# dw08aRev3.net
KiCad netlist of a schematic drawn in EAGLE
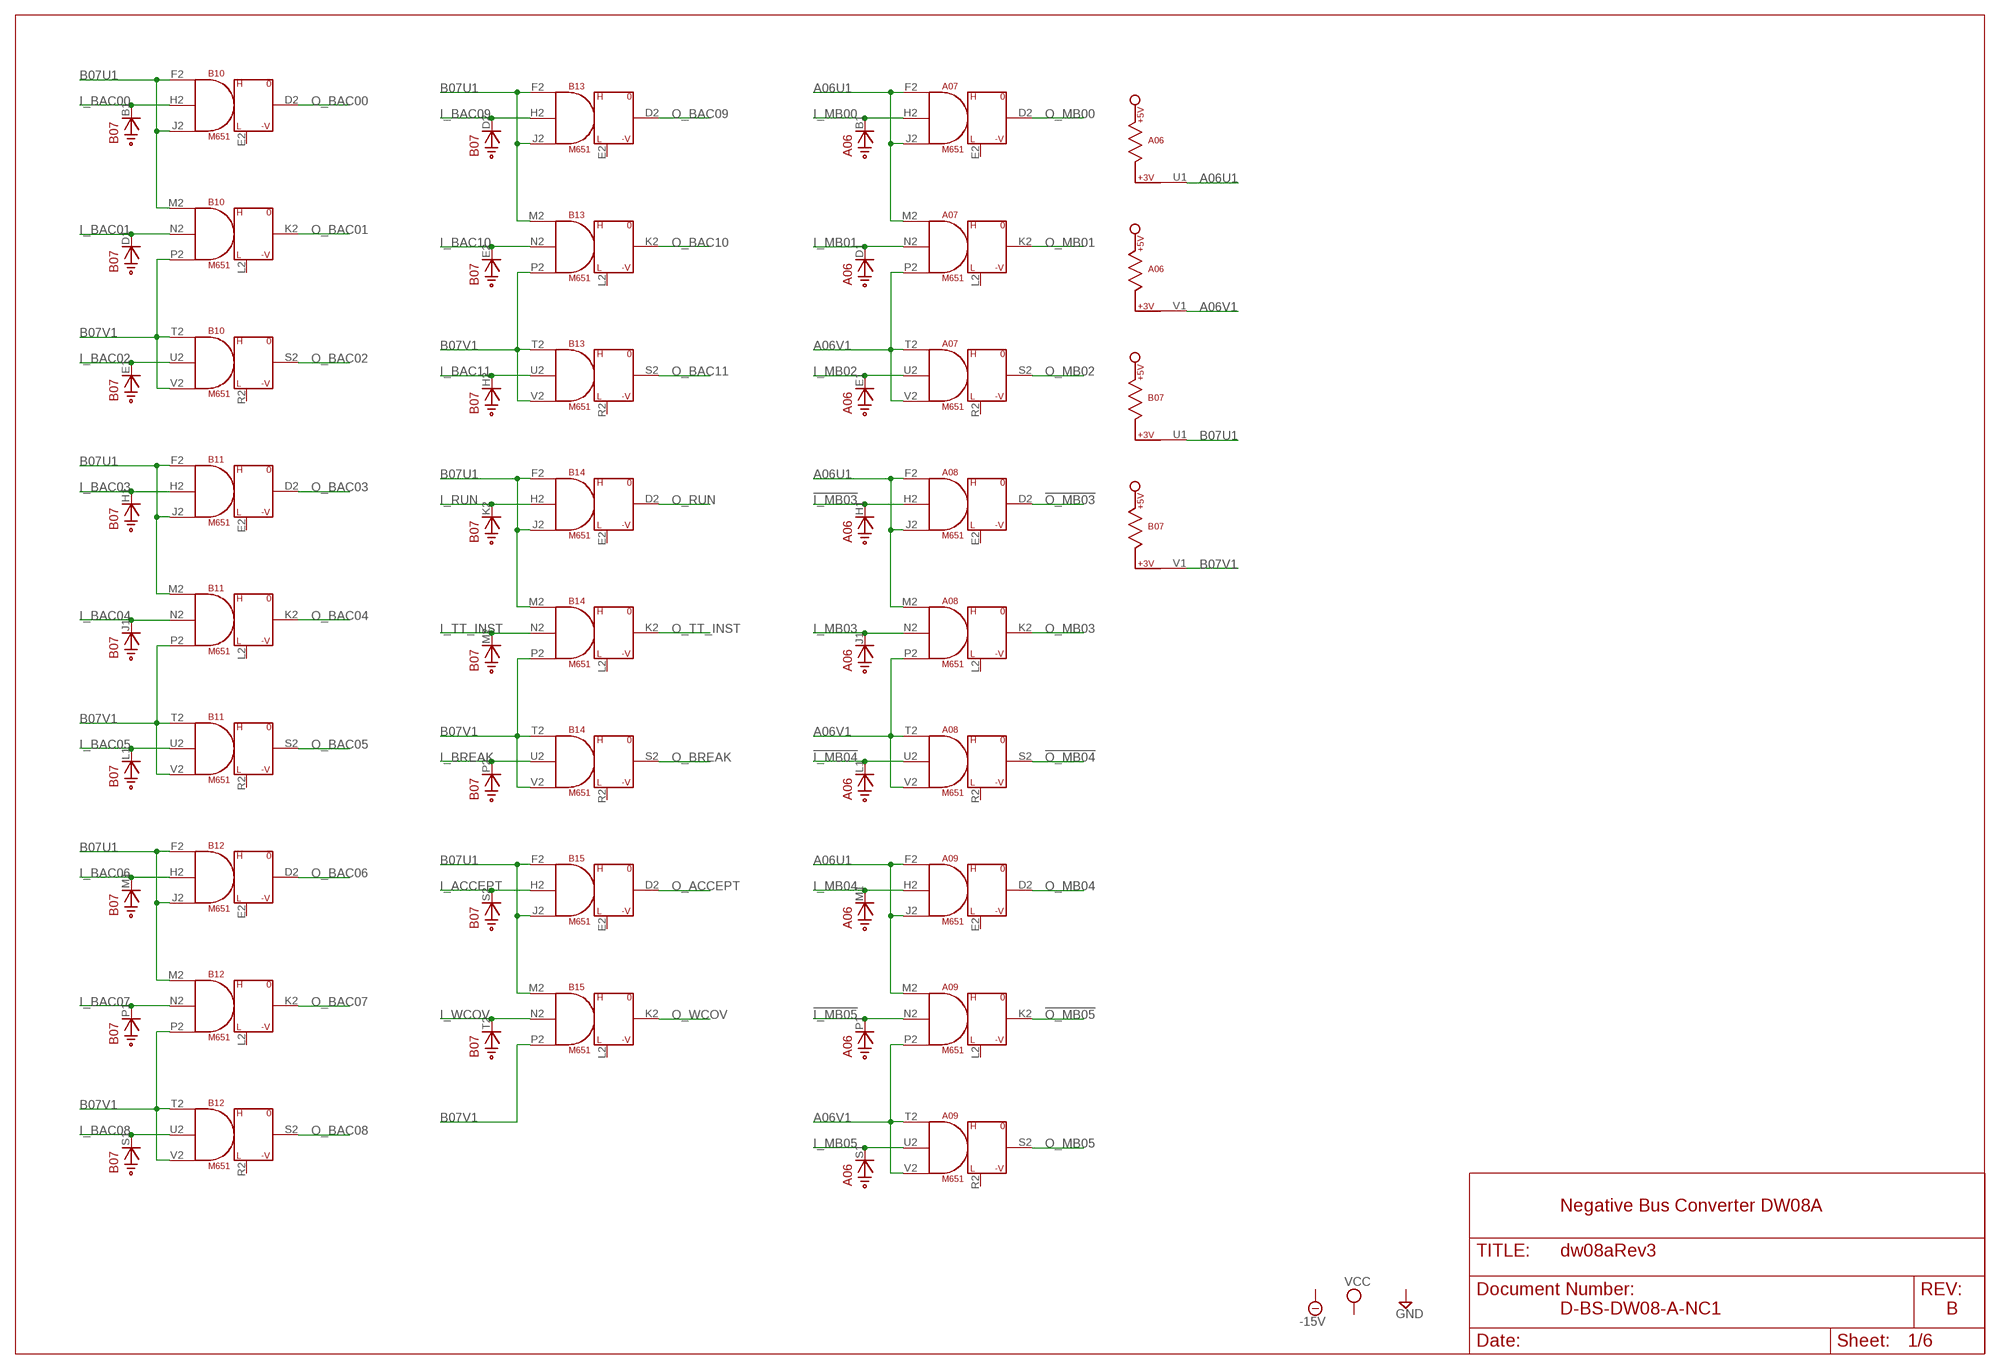
[diagram p0: schematic, sheet 1]
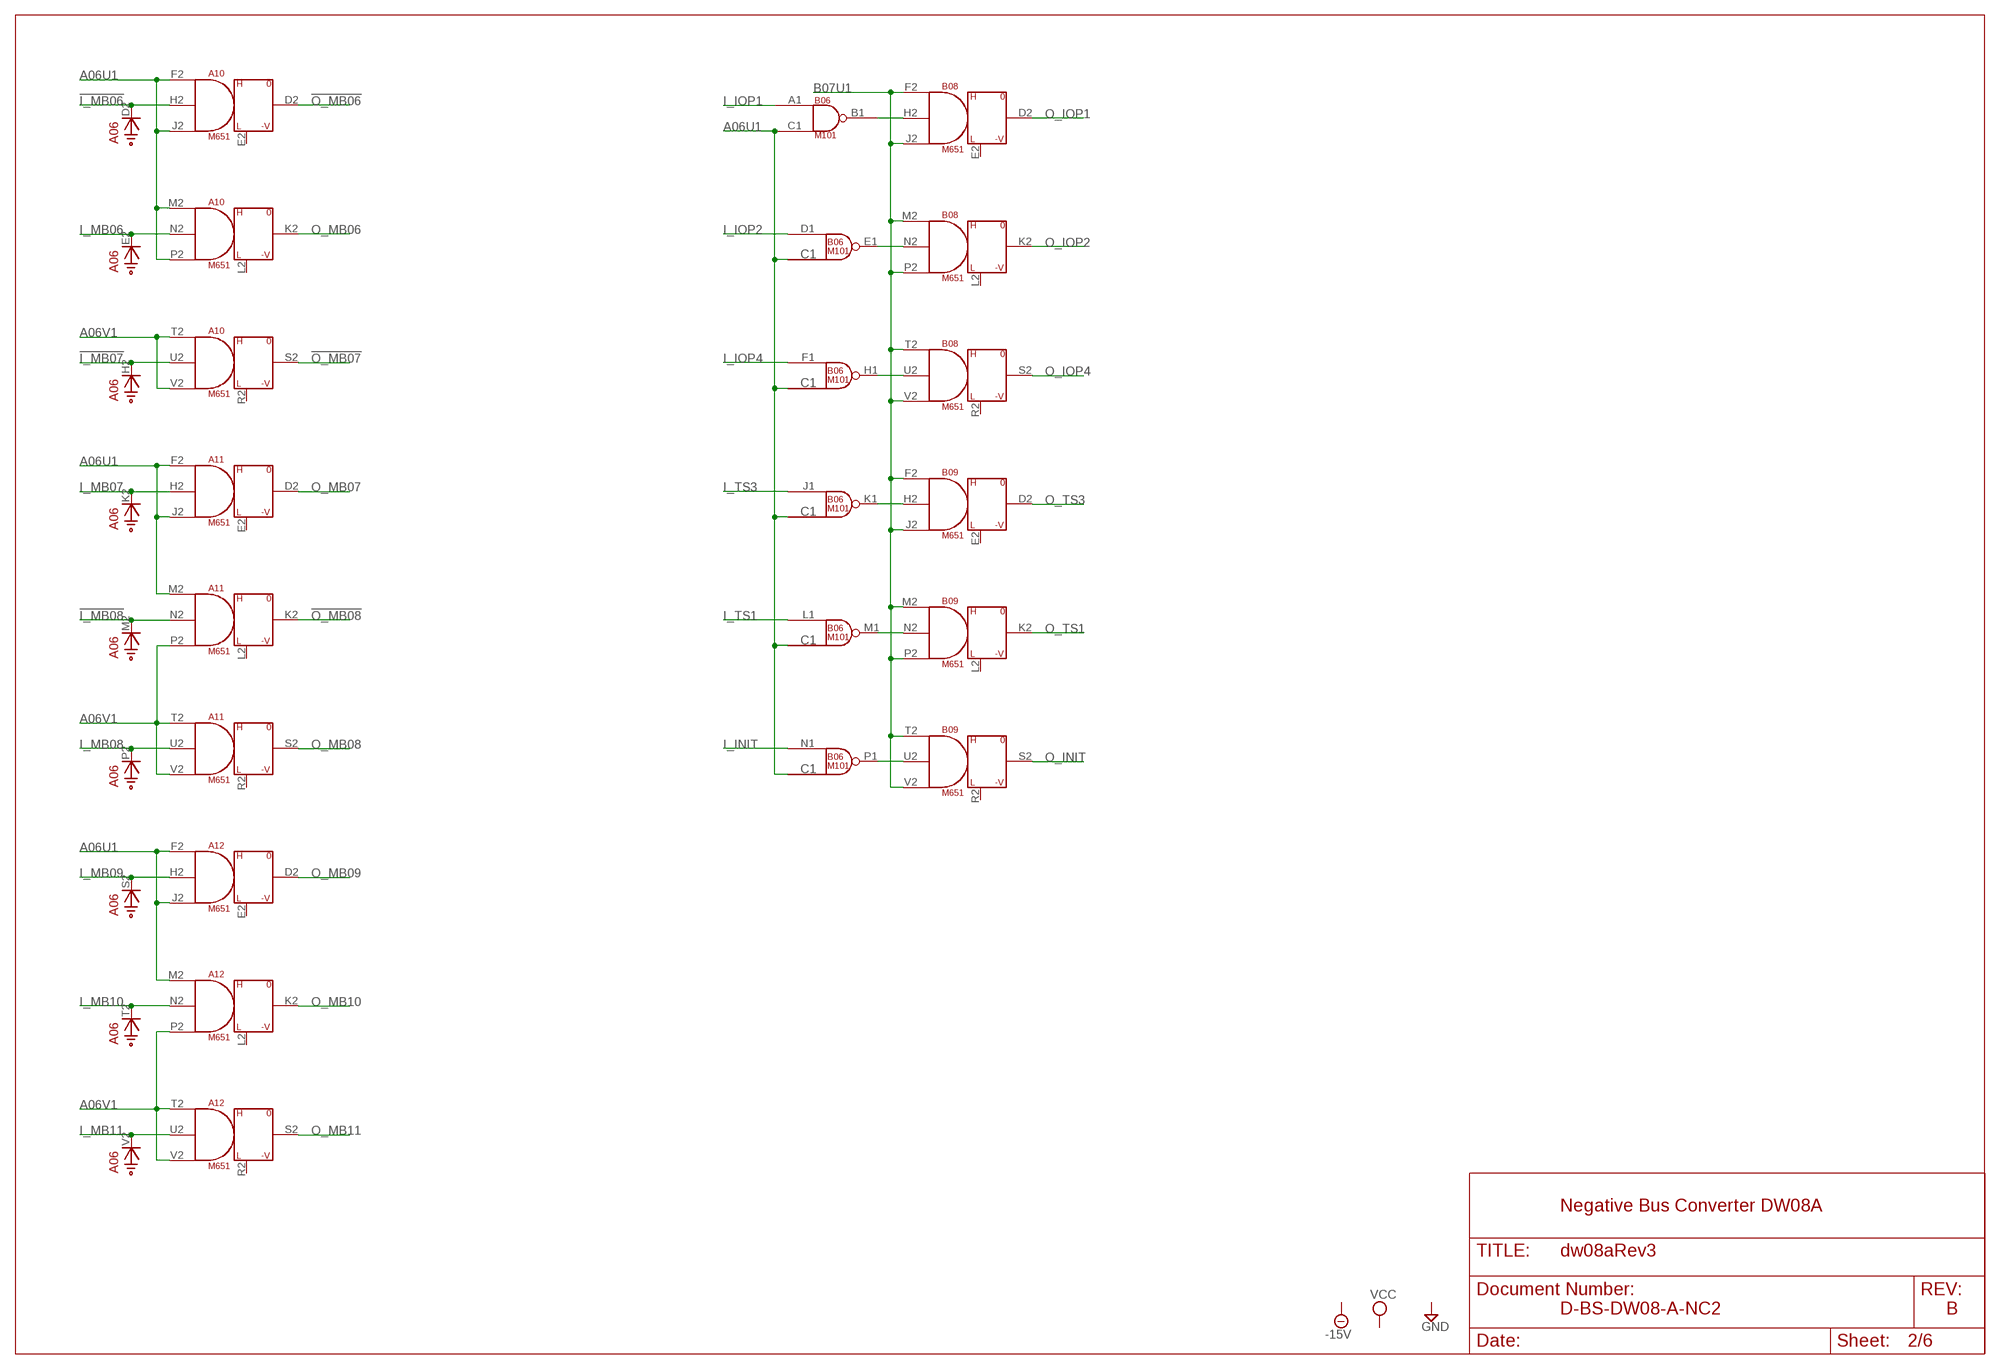
[diagram p1: schematic, sheet 2]
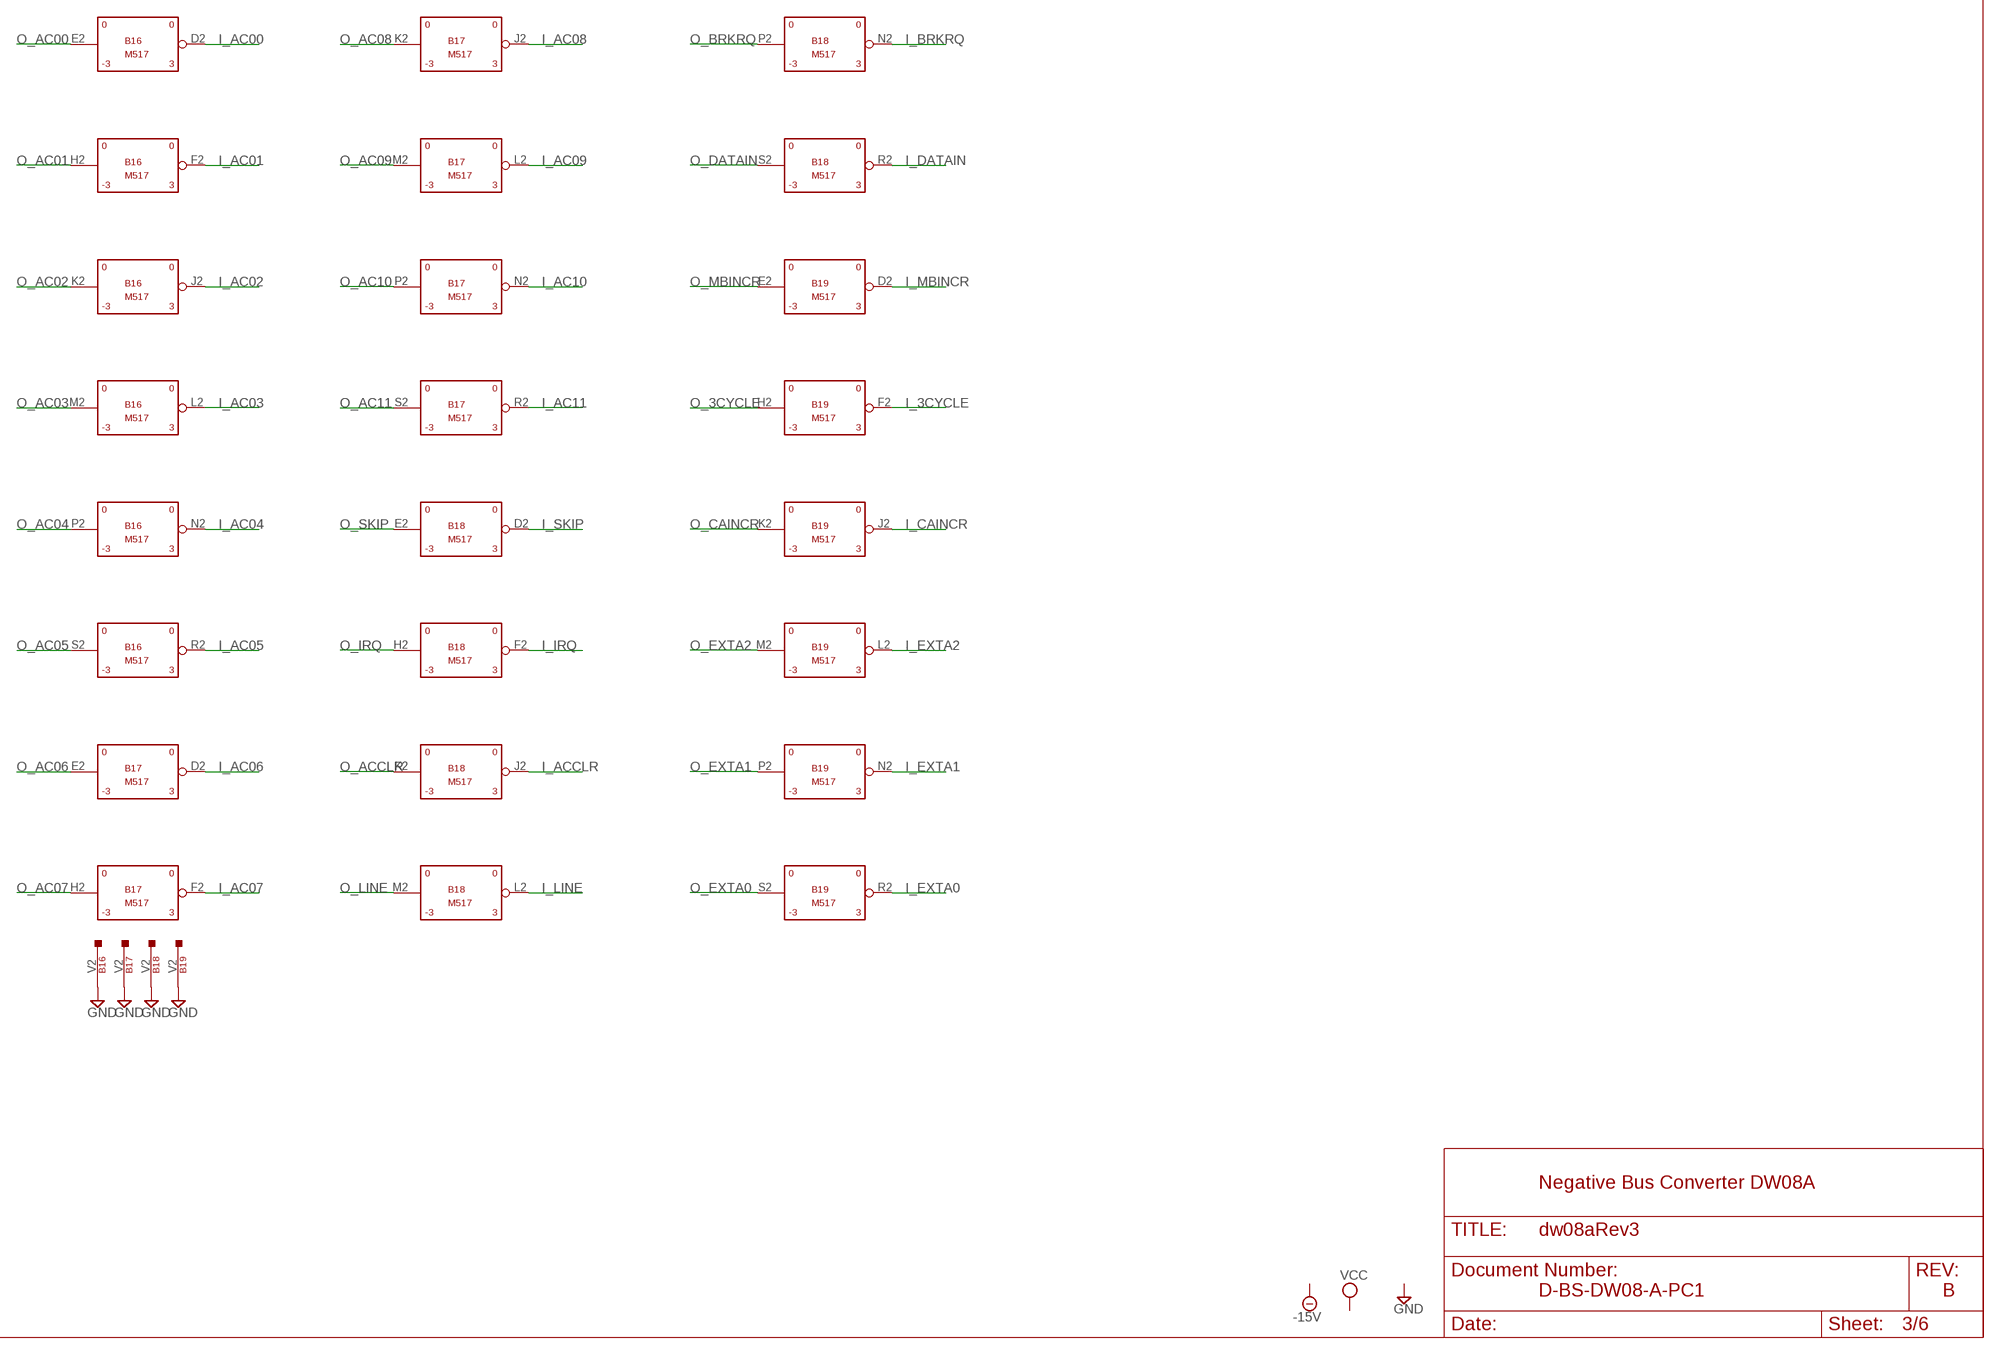
[diagram p2: schematic, sheet 3]
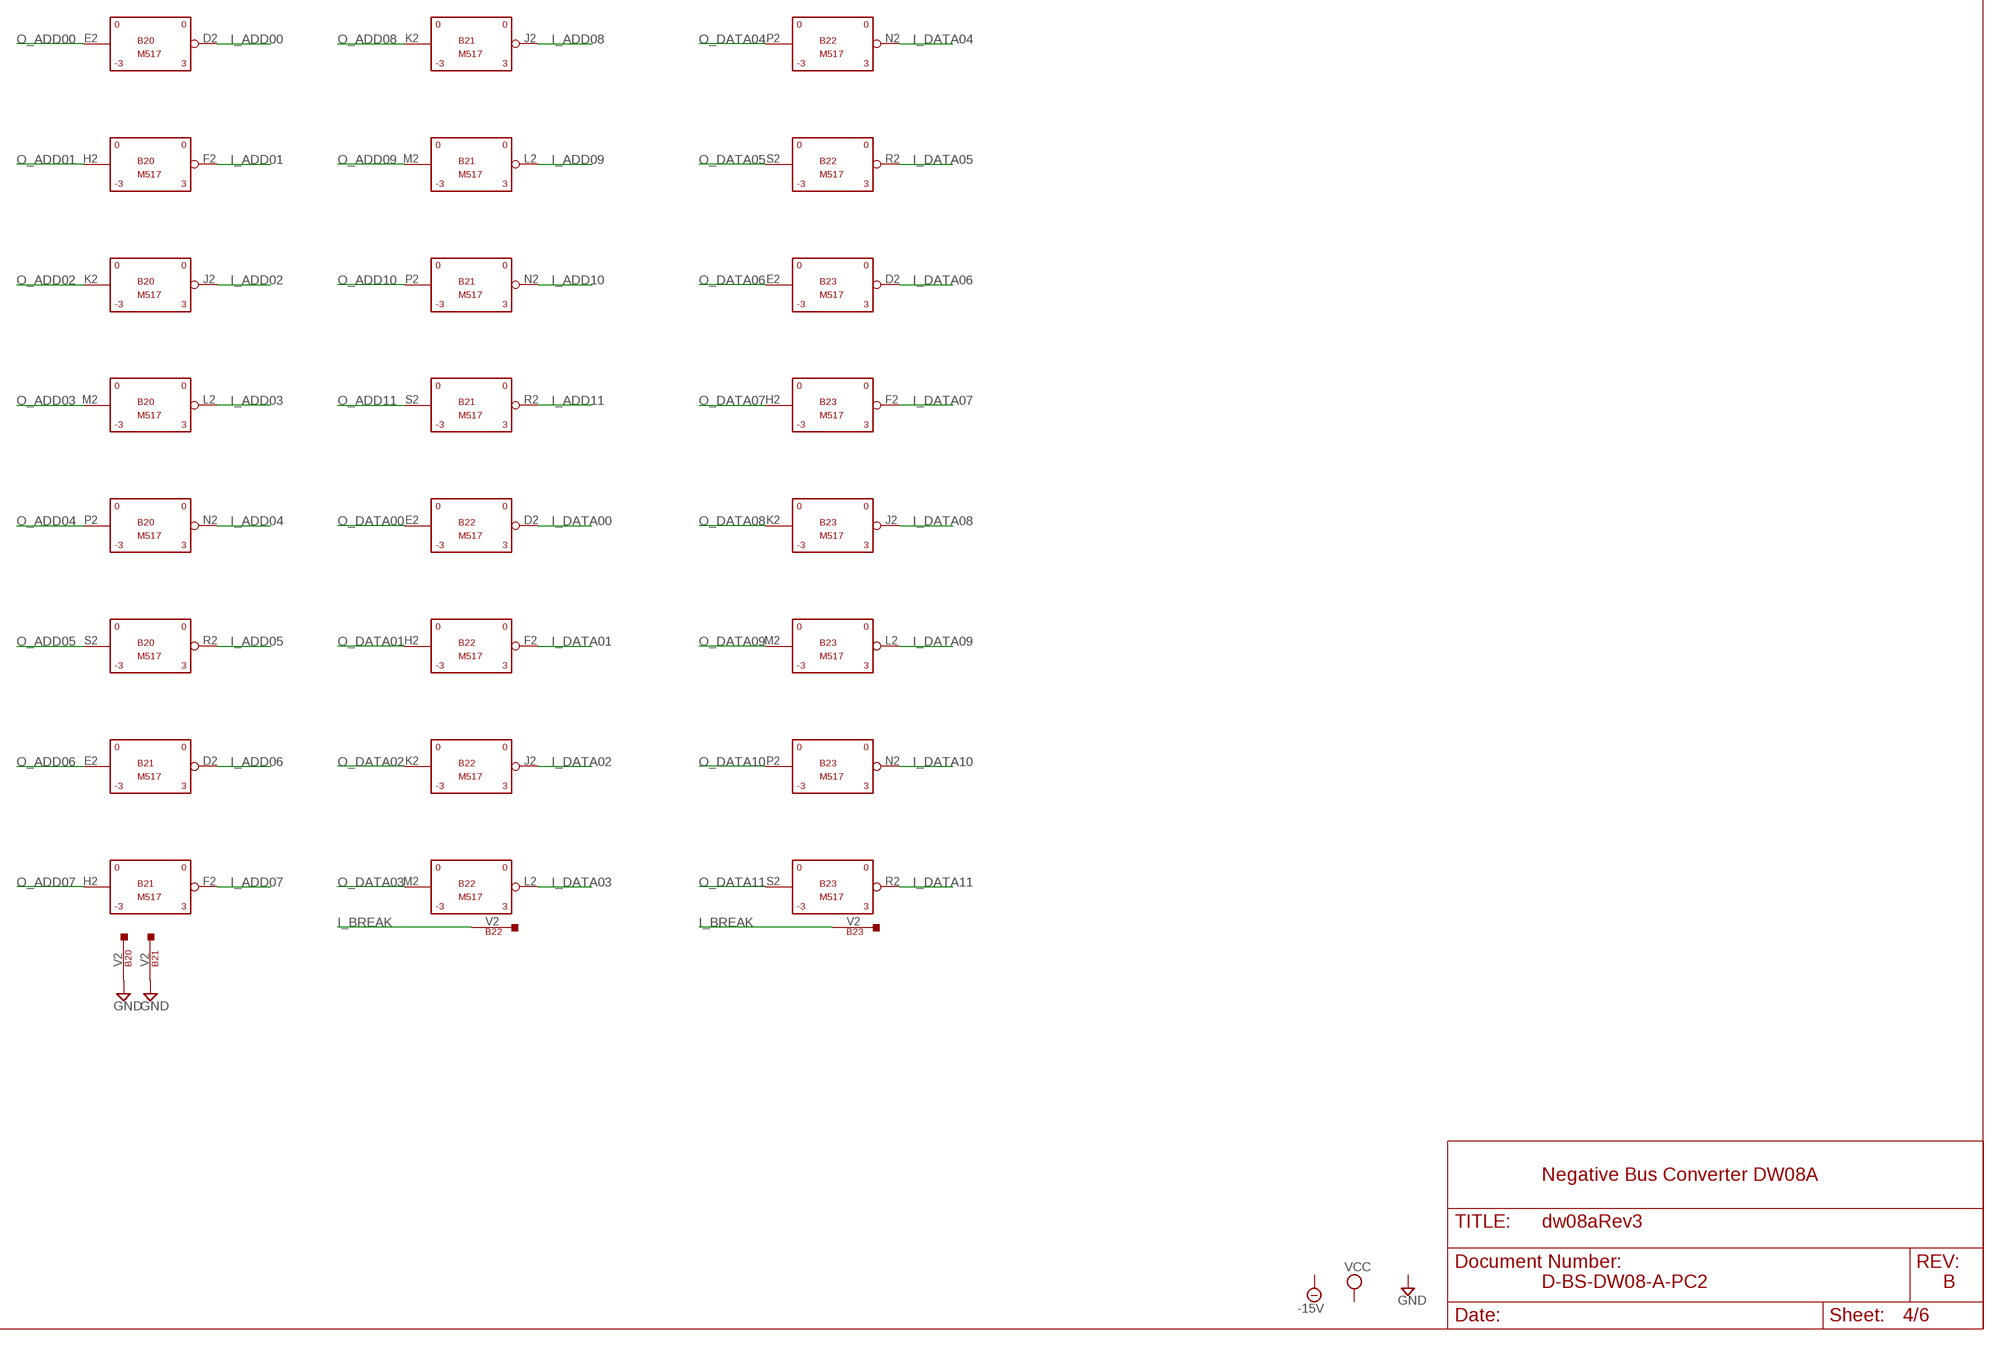
[diagram p3: schematic, sheet 4]
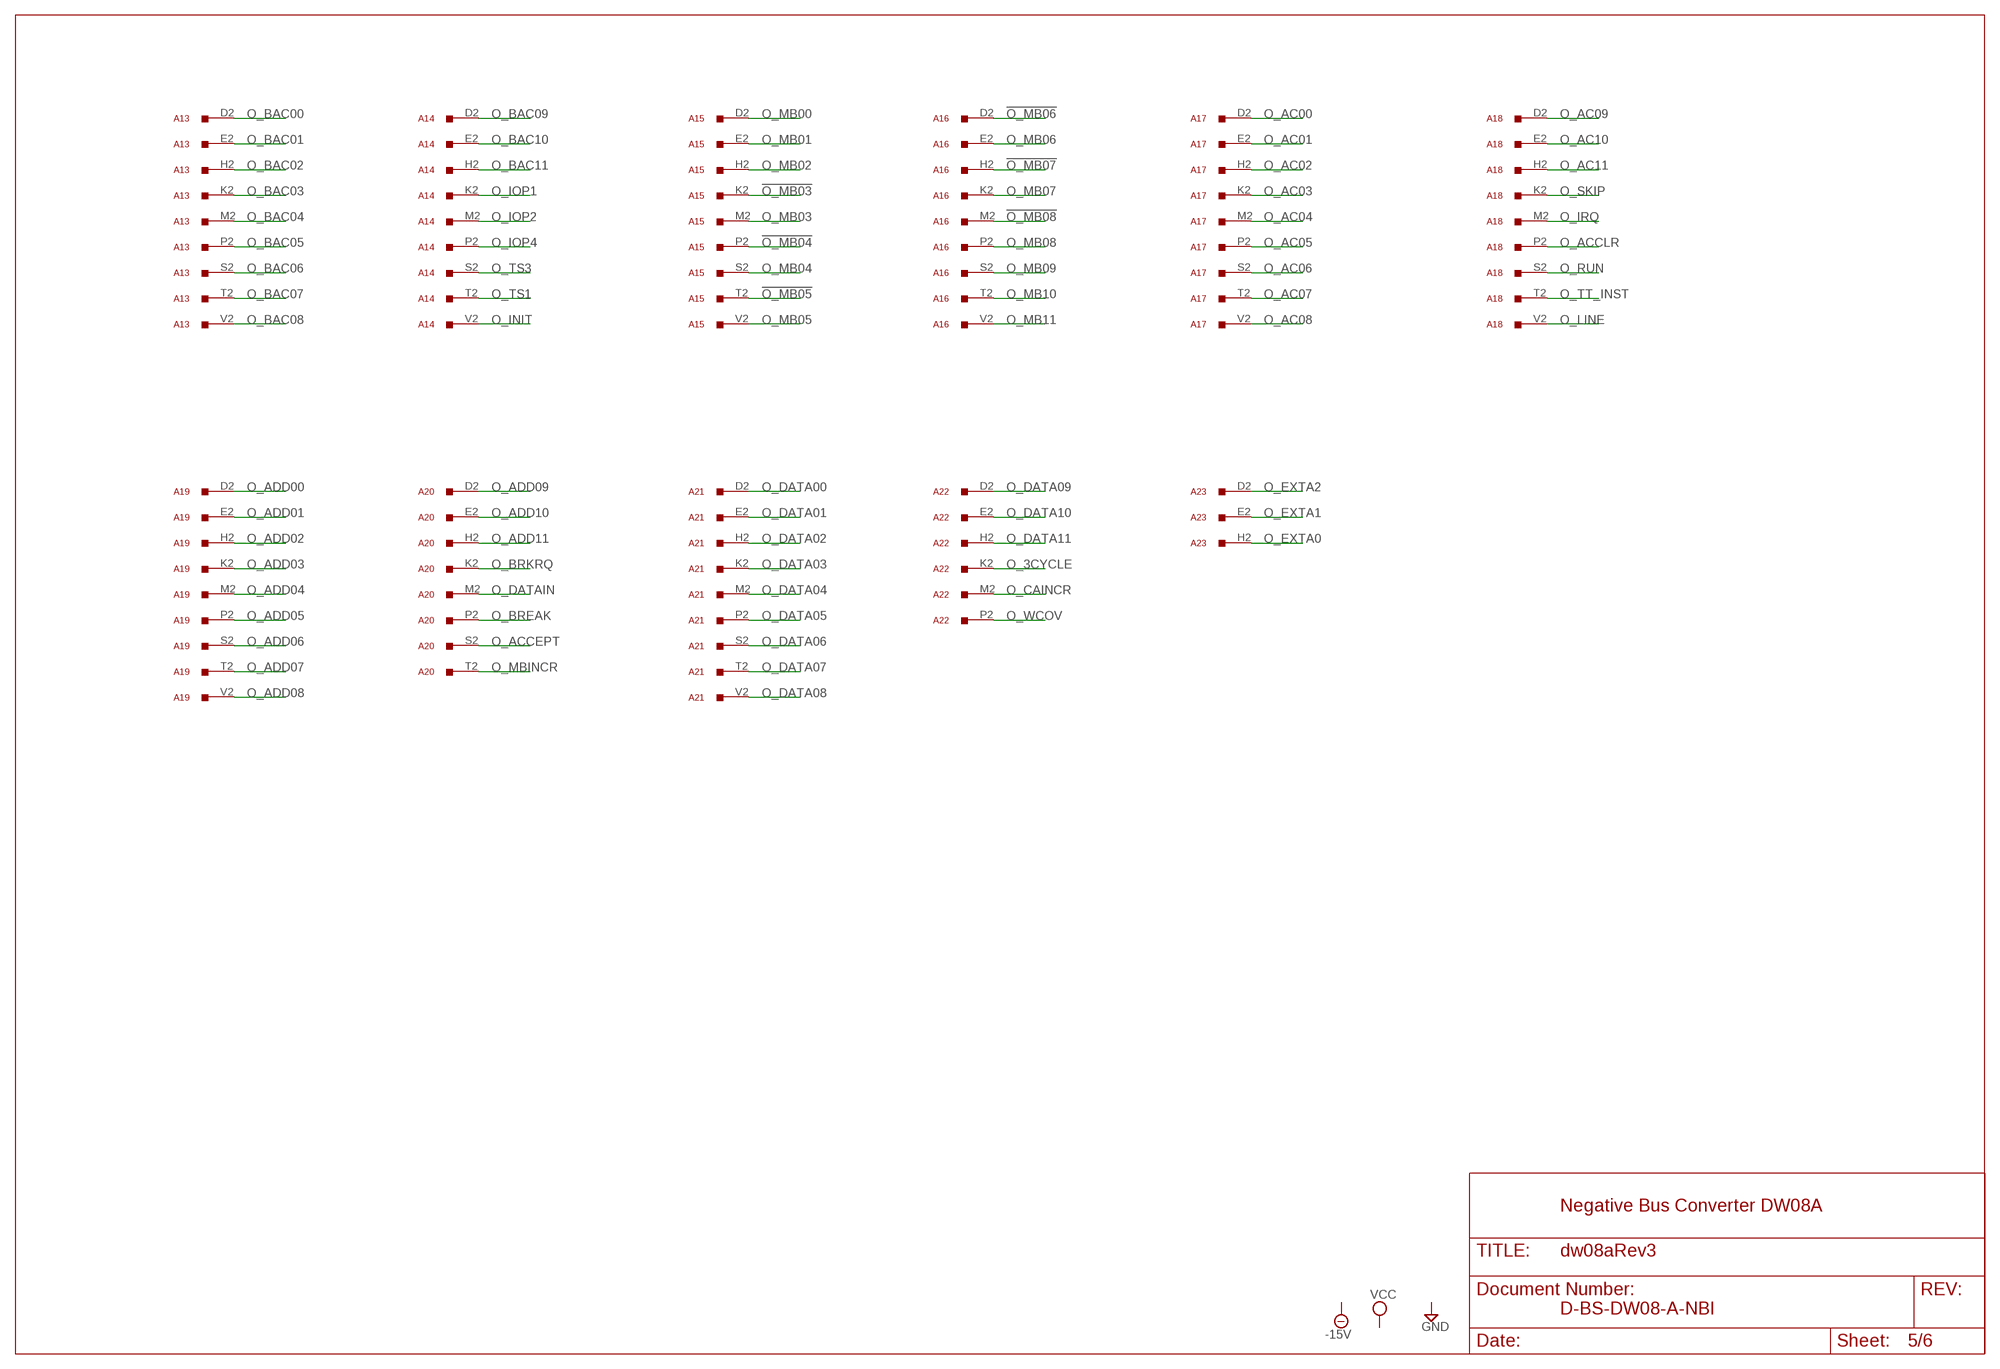
[diagram p4: schematic, sheet 5]
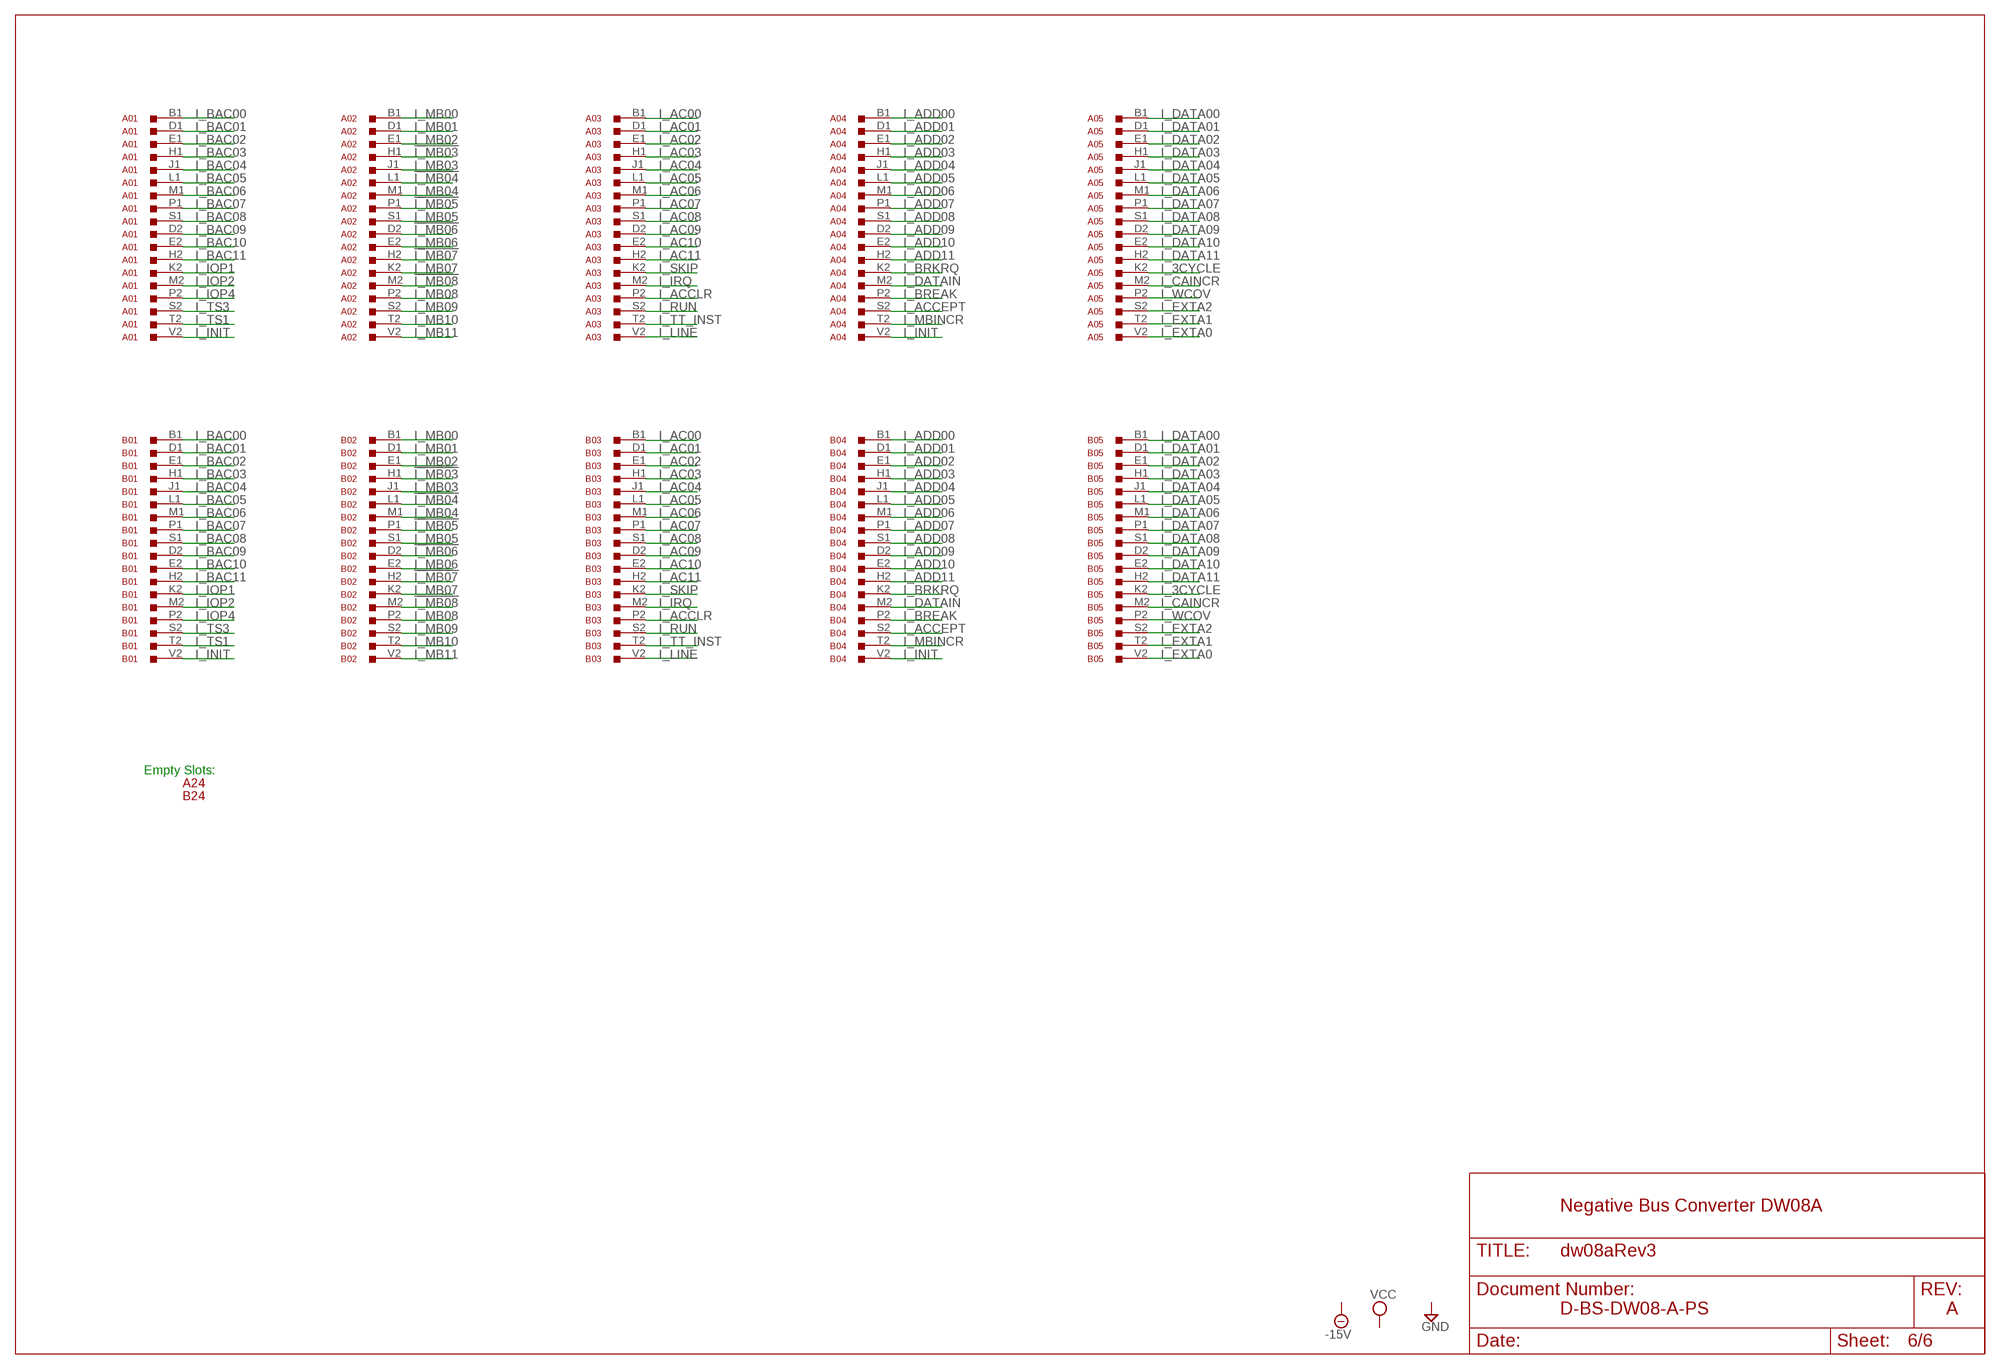
[diagram p5: schematic, sheet 6]

(export (version "E")
  (design (tool "Eeschema 10.0.6"))
  (components
    (comp (ref "B20")
      (value "M517")
      (footprint "eagle-import:H807")
      (libsource (lib "eagle-import") (part "M517"))
    )
    (comp (ref "B21")
      (value "M517")
      (footprint "eagle-import:H807")
      (libsource (lib "eagle-import") (part "M517"))
    )
    (comp (ref "B22")
      (value "M517")
      (footprint "eagle-import:H807")
      (libsource (lib "eagle-import") (part "M517"))
    )
    (comp (ref "B23")
      (value "M517")
      (footprint "eagle-import:H807")
      (libsource (lib "eagle-import") (part "M517"))
    )
    (comp (ref "B16")
      (value "M517")
      (footprint "eagle-import:H807")
      (libsource (lib "eagle-import") (part "M517"))
    )
    (comp (ref "B17")
      (value "M517")
      (footprint "eagle-import:H807")
      (libsource (lib "eagle-import") (part "M517"))
    )
    (comp (ref "B18")
      (value "M517")
      (footprint "eagle-import:H807")
      (libsource (lib "eagle-import") (part "M517"))
    )
    (comp (ref "B19")
      (value "M517")
      (footprint "eagle-import:H807")
      (libsource (lib "eagle-import") (part "M517"))
    )
    (comp (ref "A13")
      (value "W011")
      (footprint "eagle-import:H807")
      (libsource (lib "eagle-import") (part "W011"))
    )
    (comp (ref "A14")
      (value "W011")
      (footprint "eagle-import:H807")
      (libsource (lib "eagle-import") (part "W011"))
    )
    (comp (ref "A15")
      (value "W011")
      (footprint "eagle-import:H807")
      (libsource (lib "eagle-import") (part "W011"))
    )
    (comp (ref "A16")
      (value "W011")
      (footprint "eagle-import:H807")
      (libsource (lib "eagle-import") (part "W011"))
    )
    (comp (ref "A17")
      (value "W011")
      (footprint "eagle-import:H807")
      (libsource (lib "eagle-import") (part "W011"))
    )
    (comp (ref "A18")
      (value "W011")
      (footprint "eagle-import:H807")
      (libsource (lib "eagle-import") (part "W011"))
    )
    (comp (ref "A19")
      (value "W011")
      (footprint "eagle-import:H807")
      (libsource (lib "eagle-import") (part "W011"))
    )
    (comp (ref "A20")
      (value "W011")
      (footprint "eagle-import:H807")
      (libsource (lib "eagle-import") (part "W011"))
    )
    (comp (ref "A21")
      (value "W011")
      (footprint "eagle-import:H807")
      (libsource (lib "eagle-import") (part "W011"))
    )
    (comp (ref "A22")
      (value "W011")
      (footprint "eagle-import:H807")
      (libsource (lib "eagle-import") (part "W011"))
    )
    (comp (ref "A23")
      (value "W011")
      (footprint "eagle-import:H807")
      (libsource (lib "eagle-import") (part "W011"))
    )
    (comp (ref "A06")
      (value "M907")
      (footprint "eagle-import:H807")
      (libsource (lib "eagle-import") (part "M907"))
    )
    (comp (ref "A10")
      (value "M651")
      (footprint "eagle-import:H807")
      (libsource (lib "eagle-import") (part "M651"))
    )
    (comp (ref "A11")
      (value "M651")
      (footprint "eagle-import:H807")
      (libsource (lib "eagle-import") (part "M651"))
    )
    (comp (ref "A12")
      (value "M651")
      (footprint "eagle-import:H807")
      (libsource (lib "eagle-import") (part "M651"))
    )
    (comp (ref "B06")
      (value "M101")
      (footprint "eagle-import:H807")
      (libsource (lib "eagle-import") (part "M101"))
    )
    (comp (ref "B08")
      (value "M651")
      (footprint "eagle-import:H807")
      (libsource (lib "eagle-import") (part "M651"))
    )
    (comp (ref "B09")
      (value "M651")
      (footprint "eagle-import:H807")
      (libsource (lib "eagle-import") (part "M651"))
    )
    (comp (ref "A07")
      (value "M651")
      (footprint "eagle-import:H807")
      (libsource (lib "eagle-import") (part "M651"))
    )
    (comp (ref "A08")
      (value "M651")
      (footprint "eagle-import:H807")
      (libsource (lib "eagle-import") (part "M651"))
    )
    (comp (ref "A09")
      (value "M651")
      (footprint "eagle-import:H807")
      (libsource (lib "eagle-import") (part "M651"))
    )
    (comp (ref "B07")
      (value "M907")
      (footprint "eagle-import:H807")
      (libsource (lib "eagle-import") (part "M907"))
    )
    (comp (ref "B10")
      (value "M651")
      (footprint "eagle-import:H807")
      (libsource (lib "eagle-import") (part "M651"))
    )
    (comp (ref "B11")
      (value "M651")
      (footprint "eagle-import:H807")
      (libsource (lib "eagle-import") (part "M651"))
    )
    (comp (ref "B12")
      (value "M651")
      (footprint "eagle-import:H807")
      (libsource (lib "eagle-import") (part "M651"))
    )
    (comp (ref "B13")
      (value "M651")
      (footprint "eagle-import:H807")
      (libsource (lib "eagle-import") (part "M651"))
    )
    (comp (ref "B14")
      (value "M651")
      (footprint "eagle-import:H807")
      (libsource (lib "eagle-import") (part "M651"))
    )
    (comp (ref "B15")
      (value "M651")
      (footprint "eagle-import:H807")
      (libsource (lib "eagle-import") (part "M651"))
    )
    (comp (ref "A01")
      (value "M903")
      (footprint "eagle-import:H807")
      (libsource (lib "eagle-import") (part "M903"))
    )
    (comp (ref "A02")
      (value "M903")
      (footprint "eagle-import:H807")
      (libsource (lib "eagle-import") (part "M903"))
    )
    (comp (ref "A03")
      (value "M903")
      (footprint "eagle-import:H807")
      (libsource (lib "eagle-import") (part "M903"))
    )
    (comp (ref "A04")
      (value "M903")
      (footprint "eagle-import:H807")
      (libsource (lib "eagle-import") (part "M903"))
    )
    (comp (ref "A05")
      (value "M903")
      (footprint "eagle-import:H807")
      (libsource (lib "eagle-import") (part "M903"))
    )
    (comp (ref "A24")
      (value "H807")
      (footprint "eagle-import:H807")
      (libsource (lib "eagle-import") (part "H807"))
    )
    (comp (ref "B01")
      (value "M903")
      (footprint "eagle-import:H807")
      (libsource (lib "eagle-import") (part "M903"))
    )
    (comp (ref "B02")
      (value "M903")
      (footprint "eagle-import:H807")
      (libsource (lib "eagle-import") (part "M903"))
    )
    (comp (ref "B03")
      (value "M903")
      (footprint "eagle-import:H807")
      (libsource (lib "eagle-import") (part "M903"))
    )
    (comp (ref "B04")
      (value "M903")
      (footprint "eagle-import:H807")
      (libsource (lib "eagle-import") (part "M903"))
    )
    (comp (ref "B05")
      (value "M903")
      (footprint "eagle-import:H807")
      (libsource (lib "eagle-import") (part "M903"))
    )
    (comp (ref "B24")
      (value "H807")
      (footprint "eagle-import:H807")
      (libsource (lib "eagle-import") (part "H807"))
    )
  )
  (nets
    (net (code "2") (name "A06U1") (class "Default")
      (node (ref "A06") (pin "U1") (pinfunction "P$1_U1") (pintype "passive"))
      (node (ref "A07") (pin "F2") (pinfunction "IN1_F2") (pintype "input"))
      (node (ref "A07") (pin "J2") (pinfunction "IN3_J2") (pintype "input"))
      (node (ref "A07") (pin "M2") (pinfunction "IN1_M2") (pintype "input"))
      (node (ref "A08") (pin "F2") (pinfunction "IN1_F2") (pintype "input"))
      (node (ref "A08") (pin "J2") (pinfunction "IN3_J2") (pintype "input"))
      (node (ref "A08") (pin "M2") (pinfunction "IN1_M2") (pintype "input"))
      (node (ref "A09") (pin "F2") (pinfunction "IN1_F2") (pintype "input"))
      (node (ref "A09") (pin "J2") (pinfunction "IN3_J2") (pintype "input"))
      (node (ref "A09") (pin "M2") (pinfunction "IN1_M2") (pintype "input"))
      (node (ref "A10") (pin "F2") (pinfunction "IN1_F2") (pintype "input"))
      (node (ref "A10") (pin "J2") (pinfunction "IN3_J2") (pintype "input"))
      (node (ref "A10") (pin "M2") (pinfunction "IN1_M2") (pintype "input"))
      (node (ref "A10") (pin "P2") (pinfunction "IN3_P2") (pintype "input"))
      (node (ref "A11") (pin "F2") (pinfunction "IN1_F2") (pintype "input"))
      (node (ref "A11") (pin "J2") (pinfunction "IN3_J2") (pintype "input"))
      (node (ref "A11") (pin "M2") (pinfunction "IN1_M2") (pintype "input"))
      (node (ref "A12") (pin "F2") (pinfunction "IN1_F2") (pintype "input"))
      (node (ref "A12") (pin "J2") (pinfunction "IN3_J2") (pintype "input"))
      (node (ref "A12") (pin "M2") (pinfunction "IN1_M2") (pintype "input"))
      (node (ref "B06") (pin "C1") (pinfunction "IN2_C1") (pintype "input"))
    )
    (net (code "3") (name "A06V1") (class "Default")
      (node (ref "A06") (pin "V1") (pinfunction "P$1_V1") (pintype "passive"))
      (node (ref "A07") (pin "P2") (pinfunction "IN3_P2") (pintype "input"))
      (node (ref "A07") (pin "T2") (pinfunction "IN1_T2") (pintype "input"))
      (node (ref "A07") (pin "V2") (pinfunction "IN3_V2") (pintype "input"))
      (node (ref "A08") (pin "P2") (pinfunction "IN3_P2") (pintype "input"))
      (node (ref "A08") (pin "T2") (pinfunction "IN1_T2") (pintype "input"))
      (node (ref "A08") (pin "V2") (pinfunction "IN3_V2") (pintype "input"))
      (node (ref "A09") (pin "P2") (pinfunction "IN3_P2") (pintype "input"))
      (node (ref "A09") (pin "T2") (pinfunction "IN1_T2") (pintype "input"))
      (node (ref "A09") (pin "V2") (pinfunction "IN3_V2") (pintype "input"))
      (node (ref "A10") (pin "T2") (pinfunction "IN1_T2") (pintype "input"))
      (node (ref "A10") (pin "V2") (pinfunction "IN3_V2") (pintype "input"))
      (node (ref "A11") (pin "P2") (pinfunction "IN3_P2") (pintype "input"))
      (node (ref "A11") (pin "T2") (pinfunction "IN1_T2") (pintype "input"))
      (node (ref "A11") (pin "V2") (pinfunction "IN3_V2") (pintype "input"))
      (node (ref "A12") (pin "P2") (pinfunction "IN3_P2") (pintype "input"))
      (node (ref "A12") (pin "T2") (pinfunction "IN1_T2") (pintype "input"))
      (node (ref "A12") (pin "V2") (pinfunction "IN3_V2") (pintype "input"))
    )
    (net (code "4") (name "B07U1") (class "Default")
      (node (ref "B07") (pin "U1") (pinfunction "P$1_U1") (pintype "passive"))
      (node (ref "B08") (pin "F2") (pinfunction "IN1_F2") (pintype "input"))
      (node (ref "B08") (pin "J2") (pinfunction "IN3_J2") (pintype "input"))
      (node (ref "B08") (pin "M2") (pinfunction "IN1_M2") (pintype "input"))
      (node (ref "B08") (pin "P2") (pinfunction "IN3_P2") (pintype "input"))
      (node (ref "B08") (pin "T2") (pinfunction "IN1_T2") (pintype "input"))
      (node (ref "B08") (pin "V2") (pinfunction "IN3_V2") (pintype "input"))
      (node (ref "B09") (pin "F2") (pinfunction "IN1_F2") (pintype "input"))
      (node (ref "B09") (pin "J2") (pinfunction "IN3_J2") (pintype "input"))
      (node (ref "B09") (pin "M2") (pinfunction "IN1_M2") (pintype "input"))
      (node (ref "B09") (pin "P2") (pinfunction "IN3_P2") (pintype "input"))
      (node (ref "B09") (pin "T2") (pinfunction "IN1_T2") (pintype "input"))
      (node (ref "B09") (pin "V2") (pinfunction "IN3_V2") (pintype "input"))
      (node (ref "B10") (pin "F2") (pinfunction "IN1_F2") (pintype "input"))
      (node (ref "B10") (pin "J2") (pinfunction "IN3_J2") (pintype "input"))
      (node (ref "B10") (pin "M2") (pinfunction "IN1_M2") (pintype "input"))
      (node (ref "B11") (pin "F2") (pinfunction "IN1_F2") (pintype "input"))
      (node (ref "B11") (pin "J2") (pinfunction "IN3_J2") (pintype "input"))
      (node (ref "B11") (pin "M2") (pinfunction "IN1_M2") (pintype "input"))
      (node (ref "B12") (pin "F2") (pinfunction "IN1_F2") (pintype "input"))
      (node (ref "B12") (pin "J2") (pinfunction "IN3_J2") (pintype "input"))
      (node (ref "B12") (pin "M2") (pinfunction "IN1_M2") (pintype "input"))
      (node (ref "B13") (pin "F2") (pinfunction "IN1_F2") (pintype "input"))
      (node (ref "B13") (pin "J2") (pinfunction "IN3_J2") (pintype "input"))
      (node (ref "B13") (pin "M2") (pinfunction "IN1_M2") (pintype "input"))
      (node (ref "B14") (pin "F2") (pinfunction "IN1_F2") (pintype "input"))
      (node (ref "B14") (pin "J2") (pinfunction "IN3_J2") (pintype "input"))
      (node (ref "B14") (pin "M2") (pinfunction "IN1_M2") (pintype "input"))
      (node (ref "B15") (pin "F2") (pinfunction "IN1_F2") (pintype "input"))
      (node (ref "B15") (pin "J2") (pinfunction "IN3_J2") (pintype "input"))
      (node (ref "B15") (pin "M2") (pinfunction "IN1_M2") (pintype "input"))
    )
    (net (code "5") (name "B07V1") (class "Default")
      (node (ref "B07") (pin "V1") (pinfunction "P$1_V1") (pintype "passive"))
      (node (ref "B10") (pin "P2") (pinfunction "IN3_P2") (pintype "input"))
      (node (ref "B10") (pin "T2") (pinfunction "IN1_T2") (pintype "input"))
      (node (ref "B10") (pin "V2") (pinfunction "IN3_V2") (pintype "input"))
      (node (ref "B11") (pin "P2") (pinfunction "IN3_P2") (pintype "input"))
      (node (ref "B11") (pin "T2") (pinfunction "IN1_T2") (pintype "input"))
      (node (ref "B11") (pin "V2") (pinfunction "IN3_V2") (pintype "input"))
      (node (ref "B12") (pin "P2") (pinfunction "IN3_P2") (pintype "input"))
      (node (ref "B12") (pin "T2") (pinfunction "IN1_T2") (pintype "input"))
      (node (ref "B12") (pin "V2") (pinfunction "IN3_V2") (pintype "input"))
      (node (ref "B13") (pin "P2") (pinfunction "IN3_P2") (pintype "input"))
      (node (ref "B13") (pin "T2") (pinfunction "IN1_T2") (pintype "input"))
      (node (ref "B13") (pin "V2") (pinfunction "IN3_V2") (pintype "input"))
      (node (ref "B14") (pin "P2") (pinfunction "IN3_P2") (pintype "input"))
      (node (ref "B14") (pin "T2") (pinfunction "IN1_T2") (pintype "input"))
      (node (ref "B14") (pin "V2") (pinfunction "IN3_V2") (pintype "input"))
      (node (ref "B15") (pin "P2") (pinfunction "IN3_P2") (pintype "input"))
    )
    (net (code "6") (name "GND") (class "Default")
      (node (ref "B16") (pin "V2") (pinfunction "P$1_V2") (pintype "input"))
      (node (ref "B17") (pin "V2") (pinfunction "P$1_V2") (pintype "input"))
      (node (ref "B18") (pin "V2") (pinfunction "P$1_V2") (pintype "input"))
      (node (ref "B19") (pin "V2") (pinfunction "P$1_V2") (pintype "input"))
      (node (ref "B20") (pin "V2") (pinfunction "P$1_V2") (pintype "input"))
      (node (ref "B21") (pin "V2") (pinfunction "P$1_V2") (pintype "input"))
    )
    (net (code "7") (name "I_3CYCLE") (class "Default")
      (node (ref "A05") (pin "K2") (pinfunction "P$2_K2") (pintype "bidirectional"))
      (node (ref "B05") (pin "K2") (pinfunction "P$2_K2") (pintype "bidirectional"))
      (node (ref "B19") (pin "F2") (pinfunction "OUT_F2") (pintype "output"))
    )
    (net (code "8") (name "I_AC00") (class "Default")
      (node (ref "A03") (pin "B1") (pinfunction "P$2_B1") (pintype "bidirectional"))
      (node (ref "B03") (pin "B1") (pinfunction "P$2_B1") (pintype "bidirectional"))
      (node (ref "B16") (pin "D2") (pinfunction "OUT_D2") (pintype "output"))
    )
    (net (code "9") (name "I_AC01") (class "Default")
      (node (ref "A03") (pin "D1") (pinfunction "P$2_D1") (pintype "bidirectional"))
      (node (ref "B03") (pin "D1") (pinfunction "P$2_D1") (pintype "bidirectional"))
      (node (ref "B16") (pin "F2") (pinfunction "OUT_F2") (pintype "output"))
    )
    (net (code "10") (name "I_AC02") (class "Default")
      (node (ref "A03") (pin "E1") (pinfunction "P$2_E1") (pintype "bidirectional"))
      (node (ref "B03") (pin "E1") (pinfunction "P$2_E1") (pintype "bidirectional"))
      (node (ref "B16") (pin "J2") (pinfunction "OUT_J2") (pintype "output"))
    )
    (net (code "11") (name "I_AC03") (class "Default")
      (node (ref "A03") (pin "H1") (pinfunction "P$2_H1") (pintype "bidirectional"))
      (node (ref "B03") (pin "H1") (pinfunction "P$2_H1") (pintype "bidirectional"))
      (node (ref "B16") (pin "L2") (pinfunction "OUT_L2") (pintype "output"))
    )
    (net (code "12") (name "I_AC04") (class "Default")
      (node (ref "A03") (pin "J1") (pinfunction "P$2_J1") (pintype "bidirectional"))
      (node (ref "B03") (pin "J1") (pinfunction "P$2_J1") (pintype "bidirectional"))
      (node (ref "B16") (pin "N2") (pinfunction "OUT_N2") (pintype "output"))
    )
    (net (code "13") (name "I_AC05") (class "Default")
      (node (ref "A03") (pin "L1") (pinfunction "P$2_L1") (pintype "bidirectional"))
      (node (ref "B03") (pin "L1") (pinfunction "P$2_L1") (pintype "bidirectional"))
      (node (ref "B16") (pin "R2") (pinfunction "OUT_R2") (pintype "output"))
    )
    (net (code "14") (name "I_AC06") (class "Default")
      (node (ref "A03") (pin "M1") (pinfunction "P$2_M1") (pintype "bidirectional"))
      (node (ref "B03") (pin "M1") (pinfunction "P$2_M1") (pintype "bidirectional"))
      (node (ref "B17") (pin "D2") (pinfunction "OUT_D2") (pintype "output"))
    )
    (net (code "15") (name "I_AC07") (class "Default")
      (node (ref "A03") (pin "P1") (pinfunction "P$2_P1") (pintype "bidirectional"))
      (node (ref "B03") (pin "P1") (pinfunction "P$2_P1") (pintype "bidirectional"))
      (node (ref "B17") (pin "F2") (pinfunction "OUT_F2") (pintype "output"))
    )
    (net (code "16") (name "I_AC08") (class "Default")
      (node (ref "A03") (pin "S1") (pinfunction "P$2_S1") (pintype "bidirectional"))
      (node (ref "B03") (pin "S1") (pinfunction "P$2_S1") (pintype "bidirectional"))
      (node (ref "B17") (pin "J2") (pinfunction "OUT_J2") (pintype "output"))
    )
    (net (code "17") (name "I_AC09") (class "Default")
      (node (ref "A03") (pin "D2") (pinfunction "P$2_D2") (pintype "bidirectional"))
      (node (ref "B03") (pin "D2") (pinfunction "P$2_D2") (pintype "bidirectional"))
      (node (ref "B17") (pin "L2") (pinfunction "OUT_L2") (pintype "output"))
    )
    (net (code "18") (name "I_AC10") (class "Default")
      (node (ref "A03") (pin "E2") (pinfunction "P$2_E2") (pintype "bidirectional"))
      (node (ref "B03") (pin "E2") (pinfunction "P$2_E2") (pintype "bidirectional"))
      (node (ref "B17") (pin "N2") (pinfunction "OUT_N2") (pintype "output"))
    )
    (net (code "19") (name "I_AC11") (class "Default")
      (node (ref "A03") (pin "H2") (pinfunction "P$2_H2") (pintype "bidirectional"))
      (node (ref "B03") (pin "H2") (pinfunction "P$2_H2") (pintype "bidirectional"))
      (node (ref "B17") (pin "R2") (pinfunction "OUT_R2") (pintype "output"))
    )
    (net (code "20") (name "I_ACCEPT") (class "Default")
      (node (ref "A04") (pin "S2") (pinfunction "P$2_S2") (pintype "bidirectional"))
      (node (ref "B04") (pin "S2") (pinfunction "P$2_S2") (pintype "bidirectional"))
      (node (ref "B07") (pin "S2") (pinfunction "CATHODE_S2") (pintype "passive"))
      (node (ref "B15") (pin "H2") (pinfunction "IN2_H2") (pintype "input"))
    )
    (net (code "21") (name "I_ACCLR") (class "Default")
      (node (ref "A03") (pin "P2") (pinfunction "P$2_P2") (pintype "bidirectional"))
      (node (ref "B03") (pin "P2") (pinfunction "P$2_P2") (pintype "bidirectional"))
      (node (ref "B18") (pin "J2") (pinfunction "OUT_J2") (pintype "output"))
    )
    (net (code "22") (name "I_ADD00") (class "Default")
      (node (ref "A04") (pin "B1") (pinfunction "P$2_B1") (pintype "bidirectional"))
      (node (ref "B04") (pin "B1") (pinfunction "P$2_B1") (pintype "bidirectional"))
      (node (ref "B20") (pin "D2") (pinfunction "OUT_D2") (pintype "output"))
    )
    (net (code "23") (name "I_ADD01") (class "Default")
      (node (ref "A04") (pin "D1") (pinfunction "P$2_D1") (pintype "bidirectional"))
      (node (ref "B04") (pin "D1") (pinfunction "P$2_D1") (pintype "bidirectional"))
      (node (ref "B20") (pin "F2") (pinfunction "OUT_F2") (pintype "output"))
    )
    (net (code "24") (name "I_ADD02") (class "Default")
      (node (ref "A04") (pin "E1") (pinfunction "P$2_E1") (pintype "bidirectional"))
      (node (ref "B04") (pin "E1") (pinfunction "P$2_E1") (pintype "bidirectional"))
      (node (ref "B20") (pin "J2") (pinfunction "OUT_J2") (pintype "output"))
    )
    (net (code "25") (name "I_ADD03") (class "Default")
      (node (ref "A04") (pin "H1") (pinfunction "P$2_H1") (pintype "bidirectional"))
      (node (ref "B04") (pin "H1") (pinfunction "P$2_H1") (pintype "bidirectional"))
      (node (ref "B20") (pin "L2") (pinfunction "OUT_L2") (pintype "output"))
    )
    (net (code "26") (name "I_ADD04") (class "Default")
      (node (ref "A04") (pin "J1") (pinfunction "P$2_J1") (pintype "bidirectional"))
      (node (ref "B04") (pin "J1") (pinfunction "P$2_J1") (pintype "bidirectional"))
      (node (ref "B20") (pin "N2") (pinfunction "OUT_N2") (pintype "output"))
    )
    (net (code "27") (name "I_ADD05") (class "Default")
      (node (ref "A04") (pin "L1") (pinfunction "P$2_L1") (pintype "bidirectional"))
      (node (ref "B04") (pin "L1") (pinfunction "P$2_L1") (pintype "bidirectional"))
      (node (ref "B20") (pin "R2") (pinfunction "OUT_R2") (pintype "output"))
    )
    (net (code "28") (name "I_ADD06") (class "Default")
      (node (ref "A04") (pin "M1") (pinfunction "P$2_M1") (pintype "bidirectional"))
      (node (ref "B04") (pin "M1") (pinfunction "P$2_M1") (pintype "bidirectional"))
      (node (ref "B21") (pin "D2") (pinfunction "OUT_D2") (pintype "output"))
    )
    (net (code "29") (name "I_ADD07") (class "Default")
      (node (ref "A04") (pin "P1") (pinfunction "P$2_P1") (pintype "bidirectional"))
      (node (ref "B04") (pin "P1") (pinfunction "P$2_P1") (pintype "bidirectional"))
      (node (ref "B21") (pin "F2") (pinfunction "OUT_F2") (pintype "output"))
    )
    (net (code "30") (name "I_ADD08") (class "Default")
      (node (ref "A04") (pin "S1") (pinfunction "P$2_S1") (pintype "bidirectional"))
      (node (ref "B04") (pin "S1") (pinfunction "P$2_S1") (pintype "bidirectional"))
      (node (ref "B21") (pin "J2") (pinfunction "OUT_J2") (pintype "output"))
    )
    (net (code "31") (name "I_ADD09") (class "Default")
      (node (ref "A04") (pin "D2") (pinfunction "P$2_D2") (pintype "bidirectional"))
      (node (ref "B04") (pin "D2") (pinfunction "P$2_D2") (pintype "bidirectional"))
      (node (ref "B21") (pin "L2") (pinfunction "OUT_L2") (pintype "output"))
    )
    (net (code "32") (name "I_ADD10") (class "Default")
      (node (ref "A04") (pin "E2") (pinfunction "P$2_E2") (pintype "bidirectional"))
      (node (ref "B04") (pin "E2") (pinfunction "P$2_E2") (pintype "bidirectional"))
      (node (ref "B21") (pin "N2") (pinfunction "OUT_N2") (pintype "output"))
    )
    (net (code "33") (name "I_ADD11") (class "Default")
      (node (ref "A04") (pin "H2") (pinfunction "P$2_H2") (pintype "bidirectional"))
      (node (ref "B04") (pin "H2") (pinfunction "P$2_H2") (pintype "bidirectional"))
      (node (ref "B21") (pin "R2") (pinfunction "OUT_R2") (pintype "output"))
    )
    (net (code "34") (name "I_BAC00") (class "Default")
      (node (ref "A01") (pin "B1") (pinfunction "P$2_B1") (pintype "bidirectional"))
      (node (ref "B01") (pin "B1") (pinfunction "P$2_B1") (pintype "bidirectional"))
      (node (ref "B07") (pin "B1") (pinfunction "CATHODE_B1") (pintype "passive"))
      (node (ref "B10") (pin "H2") (pinfunction "IN2_H2") (pintype "input"))
    )
    (net (code "35") (name "I_BAC01") (class "Default")
      (node (ref "A01") (pin "D1") (pinfunction "P$2_D1") (pintype "bidirectional"))
      (node (ref "B01") (pin "D1") (pinfunction "P$2_D1") (pintype "bidirectional"))
      (node (ref "B07") (pin "D1") (pinfunction "CATHODE_D1") (pintype "passive"))
      (node (ref "B10") (pin "N2") (pinfunction "IN2_N2") (pintype "input"))
    )
    (net (code "36") (name "I_BAC02") (class "Default")
      (node (ref "A01") (pin "E1") (pinfunction "P$2_E1") (pintype "bidirectional"))
      (node (ref "B01") (pin "E1") (pinfunction "P$2_E1") (pintype "bidirectional"))
      (node (ref "B07") (pin "E1") (pinfunction "CATHODE_E1") (pintype "passive"))
      (node (ref "B10") (pin "U2") (pinfunction "IN2_U2") (pintype "input"))
    )
    (net (code "37") (name "I_BAC03") (class "Default")
      (node (ref "A01") (pin "H1") (pinfunction "P$2_H1") (pintype "bidirectional"))
      (node (ref "B01") (pin "H1") (pinfunction "P$2_H1") (pintype "bidirectional"))
      (node (ref "B07") (pin "H1") (pinfunction "CATHODE_H1") (pintype "passive"))
      (node (ref "B11") (pin "H2") (pinfunction "IN2_H2") (pintype "input"))
    )
    (net (code "38") (name "I_BAC04") (class "Default")
      (node (ref "A01") (pin "J1") (pinfunction "P$2_J1") (pintype "bidirectional"))
      (node (ref "B01") (pin "J1") (pinfunction "P$2_J1") (pintype "bidirectional"))
      (node (ref "B07") (pin "J1") (pinfunction "CATHODE_J1") (pintype "passive"))
      (node (ref "B11") (pin "N2") (pinfunction "IN2_N2") (pintype "input"))
    )
    (net (code "39") (name "I_BAC05") (class "Default")
      (node (ref "A01") (pin "L1") (pinfunction "P$2_L1") (pintype "bidirectional"))
      (node (ref "B01") (pin "L1") (pinfunction "P$2_L1") (pintype "bidirectional"))
      (node (ref "B07") (pin "L1") (pinfunction "CATHODE_L1") (pintype "passive"))
      (node (ref "B11") (pin "U2") (pinfunction "IN2_U2") (pintype "input"))
    )
    (net (code "40") (name "I_BAC06") (class "Default")
      (node (ref "A01") (pin "M1") (pinfunction "P$2_M1") (pintype "bidirectional"))
      (node (ref "B01") (pin "M1") (pinfunction "P$2_M1") (pintype "bidirectional"))
      (node (ref "B07") (pin "M1") (pinfunction "CATHODE_M1") (pintype "passive"))
      (node (ref "B12") (pin "H2") (pinfunction "IN2_H2") (pintype "input"))
    )
    (net (code "41") (name "I_BAC07") (class "Default")
      (node (ref "A01") (pin "P1") (pinfunction "P$2_P1") (pintype "bidirectional"))
      (node (ref "B01") (pin "P1") (pinfunction "P$2_P1") (pintype "bidirectional"))
      (node (ref "B07") (pin "P1") (pinfunction "CATHODE_P1") (pintype "passive"))
      (node (ref "B12") (pin "N2") (pinfunction "IN2_N2") (pintype "input"))
    )
    (net (code "42") (name "I_BAC08") (class "Default")
      (node (ref "A01") (pin "S1") (pinfunction "P$2_S1") (pintype "bidirectional"))
      (node (ref "B01") (pin "S1") (pinfunction "P$2_S1") (pintype "bidirectional"))
      (node (ref "B07") (pin "S1") (pinfunction "CATHODE_S1") (pintype "passive"))
      (node (ref "B12") (pin "U2") (pinfunction "IN2_U2") (pintype "input"))
    )
    (net (code "43") (name "I_BAC09") (class "Default")
      (node (ref "A01") (pin "D2") (pinfunction "P$2_D2") (pintype "bidirectional"))
      (node (ref "B01") (pin "D2") (pinfunction "P$2_D2") (pintype "bidirectional"))
      (node (ref "B07") (pin "D2") (pinfunction "CATHODE_D2") (pintype "passive"))
      (node (ref "B13") (pin "H2") (pinfunction "IN2_H2") (pintype "input"))
    )
    (net (code "44") (name "I_BAC10") (class "Default")
      (node (ref "A01") (pin "E2") (pinfunction "P$2_E2") (pintype "bidirectional"))
      (node (ref "B01") (pin "E2") (pinfunction "P$2_E2") (pintype "bidirectional"))
      (node (ref "B07") (pin "E2") (pinfunction "CATHODE_E2") (pintype "passive"))
      (node (ref "B13") (pin "N2") (pinfunction "IN2_N2") (pintype "input"))
    )
    (net (code "45") (name "I_BAC11") (class "Default")
      (node (ref "A01") (pin "H2") (pinfunction "P$2_H2") (pintype "bidirectional"))
      (node (ref "B01") (pin "H2") (pinfunction "P$2_H2") (pintype "bidirectional"))
      (node (ref "B07") (pin "H2") (pinfunction "CATHODE_H2") (pintype "passive"))
      (node (ref "B13") (pin "U2") (pinfunction "IN2_U2") (pintype "input"))
    )
    (net (code "46") (name "I_BREAK") (class "Default")
      (node (ref "A04") (pin "P2") (pinfunction "P$2_P2") (pintype "bidirectional"))
      (node (ref "B04") (pin "P2") (pinfunction "P$2_P2") (pintype "bidirectional"))
      (node (ref "B07") (pin "P2") (pinfunction "CATHODE_P2") (pintype "passive"))
      (node (ref "B14") (pin "U2") (pinfunction "IN2_U2") (pintype "input"))
      (node (ref "B22") (pin "V2") (pinfunction "P$1_V2") (pintype "input"))
      (node (ref "B23") (pin "V2") (pinfunction "P$1_V2") (pintype "input"))
    )
    (net (code "47") (name "I_BRKRQ") (class "Default")
      (node (ref "A04") (pin "K2") (pinfunction "P$2_K2") (pintype "bidirectional"))
      (node (ref "B04") (pin "K2") (pinfunction "P$2_K2") (pintype "bidirectional"))
      (node (ref "B18") (pin "N2") (pinfunction "OUT_N2") (pintype "output"))
    )
    (net (code "48") (name "I_CAINCR") (class "Default")
      (node (ref "A05") (pin "M2") (pinfunction "P$2_M2") (pintype "bidirectional"))
      (node (ref "B05") (pin "M2") (pinfunction "P$2_M2") (pintype "bidirectional"))
      (node (ref "B19") (pin "J2") (pinfunction "OUT_J2") (pintype "output"))
    )
    (net (code "49") (name "I_DATA00") (class "Default")
      (node (ref "A05") (pin "B1") (pinfunction "P$2_B1") (pintype "bidirectional"))
      (node (ref "B05") (pin "B1") (pinfunction "P$2_B1") (pintype "bidirectional"))
      (node (ref "B22") (pin "D2") (pinfunction "OUT_D2") (pintype "output"))
    )
    (net (code "50") (name "I_DATA01") (class "Default")
      (node (ref "A05") (pin "D1") (pinfunction "P$2_D1") (pintype "bidirectional"))
      (node (ref "B05") (pin "D1") (pinfunction "P$2_D1") (pintype "bidirectional"))
      (node (ref "B22") (pin "F2") (pinfunction "OUT_F2") (pintype "output"))
    )
    (net (code "51") (name "I_DATA02") (class "Default")
      (node (ref "A05") (pin "E1") (pinfunction "P$2_E1") (pintype "bidirectional"))
      (node (ref "B05") (pin "E1") (pinfunction "P$2_E1") (pintype "bidirectional"))
      (node (ref "B22") (pin "J2") (pinfunction "OUT_J2") (pintype "output"))
    )
    (net (code "52") (name "I_DATA03") (class "Default")
      (node (ref "A05") (pin "H1") (pinfunction "P$2_H1") (pintype "bidirectional"))
      (node (ref "B05") (pin "H1") (pinfunction "P$2_H1") (pintype "bidirectional"))
      (node (ref "B22") (pin "L2") (pinfunction "OUT_L2") (pintype "output"))
    )
    (net (code "53") (name "I_DATA04") (class "Default")
      (node (ref "A05") (pin "J1") (pinfunction "P$2_J1") (pintype "bidirectional"))
      (node (ref "B05") (pin "J1") (pinfunction "P$2_J1") (pintype "bidirectional"))
      (node (ref "B22") (pin "N2") (pinfunction "OUT_N2") (pintype "output"))
    )
    (net (code "54") (name "I_DATA05") (class "Default")
      (node (ref "A05") (pin "L1") (pinfunction "P$2_L1") (pintype "bidirectional"))
      (node (ref "B05") (pin "L1") (pinfunction "P$2_L1") (pintype "bidirectional"))
      (node (ref "B22") (pin "R2") (pinfunction "OUT_R2") (pintype "output"))
    )
    (net (code "55") (name "I_DATA06") (class "Default")
      (node (ref "A05") (pin "M1") (pinfunction "P$2_M1") (pintype "bidirectional"))
      (node (ref "B05") (pin "M1") (pinfunction "P$2_M1") (pintype "bidirectional"))
      (node (ref "B23") (pin "D2") (pinfunction "OUT_D2") (pintype "output"))
    )
    (net (code "56") (name "I_DATA07") (class "Default")
      (node (ref "A05") (pin "P1") (pinfunction "P$2_P1") (pintype "bidirectional"))
      (node (ref "B05") (pin "P1") (pinfunction "P$2_P1") (pintype "bidirectional"))
      (node (ref "B23") (pin "F2") (pinfunction "OUT_F2") (pintype "output"))
    )
    (net (code "57") (name "I_DATA08") (class "Default")
      (node (ref "A05") (pin "S1") (pinfunction "P$2_S1") (pintype "bidirectional"))
      (node (ref "B05") (pin "S1") (pinfunction "P$2_S1") (pintype "bidirectional"))
      (node (ref "B23") (pin "J2") (pinfunction "OUT_J2") (pintype "output"))
    )
    (net (code "58") (name "I_DATA09") (class "Default")
      (node (ref "A05") (pin "D2") (pinfunction "P$2_D2") (pintype "bidirectional"))
      (node (ref "B05") (pin "D2") (pinfunction "P$2_D2") (pintype "bidirectional"))
      (node (ref "B23") (pin "L2") (pinfunction "OUT_L2") (pintype "output"))
    )
    (net (code "59") (name "I_DATA10") (class "Default")
      (node (ref "A05") (pin "E2") (pinfunction "P$2_E2") (pintype "bidirectional"))
      (node (ref "B05") (pin "E2") (pinfunction "P$2_E2") (pintype "bidirectional"))
      (node (ref "B23") (pin "N2") (pinfunction "OUT_N2") (pintype "output"))
    )
    (net (code "60") (name "I_DATA11") (class "Default")
      (node (ref "A05") (pin "H2") (pinfunction "P$2_H2") (pintype "bidirectional"))
      (node (ref "B05") (pin "H2") (pinfunction "P$2_H2") (pintype "bidirectional"))
      (node (ref "B23") (pin "R2") (pinfunction "OUT_R2") (pintype "output"))
    )
    (net (code "61") (name "I_DATAIN") (class "Default")
      (node (ref "A04") (pin "M2") (pinfunction "P$2_M2") (pintype "bidirectional"))
      (node (ref "B04") (pin "M2") (pinfunction "P$2_M2") (pintype "bidirectional"))
      (node (ref "B18") (pin "R2") (pinfunction "OUT_R2") (pintype "output"))
    )
    (net (code "62") (name "I_EXTA0") (class "Default")
      (node (ref "A05") (pin "V2") (pinfunction "P$2_V2") (pintype "bidirectional"))
      (node (ref "B05") (pin "V2") (pinfunction "P$2_V2") (pintype "bidirectional"))
      (node (ref "B19") (pin "R2") (pinfunction "OUT_R2") (pintype "output"))
    )
    (net (code "63") (name "I_EXTA1") (class "Default")
      (node (ref "A05") (pin "T2") (pinfunction "P$2_T2") (pintype "bidirectional"))
      (node (ref "B05") (pin "T2") (pinfunction "P$2_T2") (pintype "bidirectional"))
      (node (ref "B19") (pin "N2") (pinfunction "OUT_N2") (pintype "output"))
    )
    (net (code "64") (name "I_EXTA2") (class "Default")
      (node (ref "A05") (pin "S2") (pinfunction "P$2_S2") (pintype "bidirectional"))
      (node (ref "B05") (pin "S2") (pinfunction "P$2_S2") (pintype "bidirectional"))
      (node (ref "B19") (pin "L2") (pinfunction "OUT_L2") (pintype "output"))
    )
    (net (code "65") (name "I_INIT") (class "Default")
      (node (ref "A01") (pin "V2") (pinfunction "P$2_V2") (pintype "bidirectional"))
      (node (ref "A04") (pin "V2") (pinfunction "P$2_V2") (pintype "bidirectional"))
      (node (ref "B01") (pin "V2") (pinfunction "P$2_V2") (pintype "bidirectional"))
      (node (ref "B04") (pin "V2") (pinfunction "P$2_V2") (pintype "bidirectional"))
      (node (ref "B06") (pin "N1") (pinfunction "IN_N1") (pintype "input"))
    )
    (net (code "66") (name "I_IOP1") (class "Default")
      (node (ref "A01") (pin "K2") (pinfunction "P$2_K2") (pintype "bidirectional"))
      (node (ref "B01") (pin "K2") (pinfunction "P$2_K2") (pintype "bidirectional"))
      (node (ref "B06") (pin "A1") (pinfunction "IN1_A1") (pintype "input"))
    )
    (net (code "67") (name "I_IOP2") (class "Default")
      (node (ref "A01") (pin "M2") (pinfunction "P$2_M2") (pintype "bidirectional"))
      (node (ref "B01") (pin "M2") (pinfunction "P$2_M2") (pintype "bidirectional"))
      (node (ref "B06") (pin "D1") (pinfunction "IN_D1") (pintype "input"))
    )
    (net (code "68") (name "I_IOP4") (class "Default")
      (node (ref "A01") (pin "P2") (pinfunction "P$2_P2") (pintype "bidirectional"))
      (node (ref "B01") (pin "P2") (pinfunction "P$2_P2") (pintype "bidirectional"))
      (node (ref "B06") (pin "F1") (pinfunction "IN_F1") (pintype "input"))
    )
    (net (code "69") (name "I_IRQ") (class "Default")
      (node (ref "A03") (pin "M2") (pinfunction "P$2_M2") (pintype "bidirectional"))
      (node (ref "B03") (pin "M2") (pinfunction "P$2_M2") (pintype "bidirectional"))
      (node (ref "B18") (pin "F2") (pinfunction "OUT_F2") (pintype "output"))
    )
    (net (code "70") (name "I_LINE") (class "Default")
      (node (ref "A03") (pin "V2") (pinfunction "P$2_V2") (pintype "bidirectional"))
      (node (ref "B03") (pin "V2") (pinfunction "P$2_V2") (pintype "bidirectional"))
      (node (ref "B18") (pin "L2") (pinfunction "OUT_L2") (pintype "output"))
    )
    (net (code "71") (name "I_MB00") (class "Default")
      (node (ref "A02") (pin "B1") (pinfunction "P$2_B1") (pintype "bidirectional"))
      (node (ref "A06") (pin "B1") (pinfunction "CATHODE_B1") (pintype "passive"))
      (node (ref "A07") (pin "H2") (pinfunction "IN2_H2") (pintype "input"))
      (node (ref "B02") (pin "B1") (pinfunction "P$2_B1") (pintype "bidirectional"))
    )
    (net (code "72") (name "I_MB01") (class "Default")
      (node (ref "A02") (pin "D1") (pinfunction "P$2_D1") (pintype "bidirectional"))
      (node (ref "A06") (pin "D1") (pinfunction "CATHODE_D1") (pintype "passive"))
      (node (ref "A07") (pin "N2") (pinfunction "IN2_N2") (pintype "input"))
      (node (ref "B02") (pin "D1") (pinfunction "P$2_D1") (pintype "bidirectional"))
    )
    (net (code "73") (name "I_MB02") (class "Default")
      (node (ref "A02") (pin "E1") (pinfunction "P$2_E1") (pintype "bidirectional"))
      (node (ref "A06") (pin "E1") (pinfunction "CATHODE_E1") (pintype "passive"))
      (node (ref "A07") (pin "U2") (pinfunction "IN2_U2") (pintype "input"))
      (node (ref "B02") (pin "E1") (pinfunction "P$2_E1") (pintype "bidirectional"))
    )
    (net (code "74") (name "I_MB03") (class "Default")
      (node (ref "A02") (pin "J1") (pinfunction "P$2_J1") (pintype "bidirectional"))
      (node (ref "A06") (pin "J1") (pinfunction "CATHODE_J1") (pintype "passive"))
      (node (ref "A08") (pin "N2") (pinfunction "IN2_N2") (pintype "input"))
      (node (ref "B02") (pin "J1") (pinfunction "P$2_J1") (pintype "bidirectional"))
    )
    (net (code "75") (name "I_MB04") (class "Default")
      (node (ref "A02") (pin "M1") (pinfunction "P$2_M1") (pintype "bidirectional"))
      (node (ref "A06") (pin "M1") (pinfunction "CATHODE_M1") (pintype "passive"))
      (node (ref "A09") (pin "H2") (pinfunction "IN2_H2") (pintype "input"))
      (node (ref "B02") (pin "M1") (pinfunction "P$2_M1") (pintype "bidirectional"))
    )
    (net (code "76") (name "I_MB05") (class "Default")
      (node (ref "A02") (pin "S1") (pinfunction "P$2_S1") (pintype "bidirectional"))
      (node (ref "A06") (pin "S1") (pinfunction "CATHODE_S1") (pintype "passive"))
      (node (ref "A09") (pin "U2") (pinfunction "IN2_U2") (pintype "input"))
      (node (ref "B02") (pin "S1") (pinfunction "P$2_S1") (pintype "bidirectional"))
    )
    (net (code "77") (name "I_MB06") (class "Default")
      (node (ref "A02") (pin "E2") (pinfunction "P$2_E2") (pintype "bidirectional"))
      (node (ref "A06") (pin "E2") (pinfunction "CATHODE_E2") (pintype "passive"))
      (node (ref "A10") (pin "N2") (pinfunction "IN2_N2") (pintype "input"))
      (node (ref "B02") (pin "E2") (pinfunction "P$2_E2") (pintype "bidirectional"))
    )
    (net (code "78") (name "I_MB07") (class "Default")
      (node (ref "A02") (pin "K2") (pinfunction "P$2_K2") (pintype "bidirectional"))
      (node (ref "A06") (pin "K2") (pinfunction "CATHODE_K2") (pintype "passive"))
      (node (ref "A11") (pin "H2") (pinfunction "IN2_H2") (pintype "input"))
      (node (ref "B02") (pin "K2") (pinfunction "P$2_K2") (pintype "bidirectional"))
    )
    (net (code "79") (name "I_MB08") (class "Default")
      (node (ref "A02") (pin "P2") (pinfunction "P$2_P2") (pintype "bidirectional"))
      (node (ref "A06") (pin "P2") (pinfunction "CATHODE_P2") (pintype "passive"))
      (node (ref "A11") (pin "U2") (pinfunction "IN2_U2") (pintype "input"))
      (node (ref "B02") (pin "P2") (pinfunction "P$2_P2") (pintype "bidirectional"))
    )
    (net (code "80") (name "I_MB09") (class "Default")
      (node (ref "A02") (pin "S2") (pinfunction "P$2_S2") (pintype "bidirectional"))
      (node (ref "A06") (pin "S2") (pinfunction "CATHODE_S2") (pintype "passive"))
      (node (ref "A12") (pin "H2") (pinfunction "IN2_H2") (pintype "input"))
      (node (ref "B02") (pin "S2") (pinfunction "P$2_S2") (pintype "bidirectional"))
    )
    (net (code "81") (name "I_MB10") (class "Default")
      (node (ref "A02") (pin "T2") (pinfunction "P$2_T2") (pintype "bidirectional"))
      (node (ref "A06") (pin "T2") (pinfunction "CATHODE_T2") (pintype "passive"))
      (node (ref "A12") (pin "N2") (pinfunction "IN2_N2") (pintype "input"))
      (node (ref "B02") (pin "T2") (pinfunction "P$2_T2") (pintype "bidirectional"))
    )
    (net (code "82") (name "I_MB11") (class "Default")
      (node (ref "A02") (pin "V2") (pinfunction "P$2_V2") (pintype "bidirectional"))
      (node (ref "A06") (pin "V2") (pinfunction "CATHODE_V2") (pintype "passive"))
      (node (ref "A12") (pin "U2") (pinfunction "IN2_U2") (pintype "input"))
      (node (ref "B02") (pin "V2") (pinfunction "P$2_V2") (pintype "bidirectional"))
    )
    (net (code "83") (name "I_MBINCR") (class "Default")
      (node (ref "A04") (pin "T2") (pinfunction "P$2_T2") (pintype "bidirectional"))
      (node (ref "B04") (pin "T2") (pinfunction "P$2_T2") (pintype "bidirectional"))
      (node (ref "B19") (pin "D2") (pinfunction "OUT_D2") (pintype "output"))
    )
    (net (code "84") (name "I_RUN") (class "Default")
      (node (ref "A03") (pin "S2") (pinfunction "P$2_S2") (pintype "bidirectional"))
      (node (ref "B03") (pin "S2") (pinfunction "P$2_S2") (pintype "bidirectional"))
      (node (ref "B07") (pin "K2") (pinfunction "CATHODE_K2") (pintype "passive"))
      (node (ref "B14") (pin "H2") (pinfunction "IN2_H2") (pintype "input"))
    )
    (net (code "85") (name "I_SKIP") (class "Default")
      (node (ref "A03") (pin "K2") (pinfunction "P$2_K2") (pintype "bidirectional"))
      (node (ref "B03") (pin "K2") (pinfunction "P$2_K2") (pintype "bidirectional"))
      (node (ref "B18") (pin "D2") (pinfunction "OUT_D2") (pintype "output"))
    )
    (net (code "86") (name "I_TS1") (class "Default")
      (node (ref "A01") (pin "T2") (pinfunction "P$2_T2") (pintype "bidirectional"))
      (node (ref "B01") (pin "T2") (pinfunction "P$2_T2") (pintype "bidirectional"))
      (node (ref "B06") (pin "L1") (pinfunction "IN_L1") (pintype "input"))
    )
    (net (code "87") (name "I_TS3") (class "Default")
      (node (ref "A01") (pin "S2") (pinfunction "P$2_S2") (pintype "bidirectional"))
      (node (ref "B01") (pin "S2") (pinfunction "P$2_S2") (pintype "bidirectional"))
      (node (ref "B06") (pin "J1") (pinfunction "IN_J1") (pintype "input"))
    )
    (net (code "88") (name "I_TT_INST") (class "Default")
      (node (ref "A03") (pin "T2") (pinfunction "P$2_T2") (pintype "bidirectional"))
      (node (ref "B03") (pin "T2") (pinfunction "P$2_T2") (pintype "bidirectional"))
      (node (ref "B07") (pin "M2") (pinfunction "CATHODE_M2") (pintype "passive"))
      (node (ref "B14") (pin "N2") (pinfunction "IN2_N2") (pintype "input"))
    )
    (net (code "89") (name "I_WCOV") (class "Default")
      (node (ref "A05") (pin "P2") (pinfunction "P$2_P2") (pintype "bidirectional"))
      (node (ref "B05") (pin "P2") (pinfunction "P$2_P2") (pintype "bidirectional"))
      (node (ref "B07") (pin "T2") (pinfunction "CATHODE_T2") (pintype "passive"))
      (node (ref "B15") (pin "N2") (pinfunction "IN2_N2") (pintype "input"))
    )
    (net (code "90") (name "Net-(B06A-OUT)") (class "Default")
      (node (ref "B06") (pin "B1") (pinfunction "OUT_B1") (pintype "output"))
      (node (ref "B08") (pin "H2") (pinfunction "IN2_H2") (pintype "input"))
    )
    (net (code "91") (name "Net-(B06B-OUT)") (class "Default")
      (node (ref "B06") (pin "E1") (pinfunction "OUT_E1") (pintype "output"))
      (node (ref "B08") (pin "N2") (pinfunction "IN2_N2") (pintype "input"))
    )
    (net (code "92") (name "Net-(B06F-OUT)") (class "Default")
      (node (ref "B06") (pin "H1") (pinfunction "OUT_H1") (pintype "output"))
      (node (ref "B08") (pin "U2") (pinfunction "IN2_U2") (pintype "input"))
    )
    (net (code "93") (name "Net-(B06H-OUT)") (class "Default")
      (node (ref "B06") (pin "K1") (pinfunction "OUT_K1") (pintype "output"))
      (node (ref "B09") (pin "H2") (pinfunction "IN2_H2") (pintype "input"))
    )
    (net (code "94") (name "Net-(B06J-OUT)") (class "Default")
      (node (ref "B06") (pin "M1") (pinfunction "OUT_M1") (pintype "output"))
      (node (ref "B09") (pin "N2") (pinfunction "IN2_N2") (pintype "input"))
    )
    (net (code "95") (name "Net-(B06L-OUT)") (class "Default")
      (node (ref "B06") (pin "P1") (pinfunction "OUT_P1") (pintype "output"))
      (node (ref "B09") (pin "U2") (pinfunction "IN2_U2") (pintype "input"))
    )
    (net (code "96") (name "O_3CYCLE") (class "Default")
      (node (ref "A22") (pin "K2") (pinfunction "P$2_K2") (pintype "bidirectional"))
      (node (ref "B19") (pin "H2") (pinfunction "IN_H2") (pintype "input"))
    )
    (net (code "97") (name "O_AC00") (class "Default")
      (node (ref "A17") (pin "D2") (pinfunction "P$2_D2") (pintype "bidirectional"))
      (node (ref "B16") (pin "E2") (pinfunction "IN_E2") (pintype "input"))
    )
    (net (code "98") (name "O_AC01") (class "Default")
      (node (ref "A17") (pin "E2") (pinfunction "P$2_E2") (pintype "bidirectional"))
      (node (ref "B16") (pin "H2") (pinfunction "IN_H2") (pintype "input"))
    )
    (net (code "99") (name "O_AC02") (class "Default")
      (node (ref "A17") (pin "H2") (pinfunction "P$2_H2") (pintype "bidirectional"))
      (node (ref "B16") (pin "K2") (pinfunction "IN_K2") (pintype "input"))
    )
    (net (code "100") (name "O_AC03") (class "Default")
      (node (ref "A17") (pin "K2") (pinfunction "P$2_K2") (pintype "bidirectional"))
      (node (ref "B16") (pin "M2") (pinfunction "IN_M2") (pintype "input"))
    )
    (net (code "101") (name "O_AC04") (class "Default")
      (node (ref "A17") (pin "M2") (pinfunction "P$2_M2") (pintype "bidirectional"))
      (node (ref "B16") (pin "P2") (pinfunction "IN_P2") (pintype "input"))
    )
    (net (code "102") (name "O_AC05") (class "Default")
      (node (ref "A17") (pin "P2") (pinfunction "P$2_P2") (pintype "bidirectional"))
      (node (ref "B16") (pin "S2") (pinfunction "IN_S2") (pintype "input"))
    )
    (net (code "103") (name "O_AC06") (class "Default")
      (node (ref "A17") (pin "S2") (pinfunction "P$2_S2") (pintype "bidirectional"))
      (node (ref "B17") (pin "E2") (pinfunction "IN_E2") (pintype "input"))
    )
    (net (code "104") (name "O_AC07") (class "Default")
      (node (ref "A17") (pin "T2") (pinfunction "P$2_T2") (pintype "bidirectional"))
      (node (ref "B17") (pin "H2") (pinfunction "IN_H2") (pintype "input"))
    )
    (net (code "105") (name "O_AC08") (class "Default")
      (node (ref "A17") (pin "V2") (pinfunction "P$2_V2") (pintype "bidirectional"))
      (node (ref "B17") (pin "K2") (pinfunction "IN_K2") (pintype "input"))
    )
    (net (code "106") (name "O_AC09") (class "Default")
      (node (ref "A18") (pin "D2") (pinfunction "P$2_D2") (pintype "bidirectional"))
      (node (ref "B17") (pin "M2") (pinfunction "IN_M2") (pintype "input"))
    )
    (net (code "107") (name "O_AC10") (class "Default")
      (node (ref "A18") (pin "E2") (pinfunction "P$2_E2") (pintype "bidirectional"))
      (node (ref "B17") (pin "P2") (pinfunction "IN_P2") (pintype "input"))
    )
    (net (code "108") (name "O_AC11") (class "Default")
      (node (ref "A18") (pin "H2") (pinfunction "P$2_H2") (pintype "bidirectional"))
      (node (ref "B17") (pin "S2") (pinfunction "IN_S2") (pintype "input"))
    )
    (net (code "109") (name "O_ACCEPT") (class "Default")
      (node (ref "A20") (pin "S2") (pinfunction "P$2_S2") (pintype "bidirectional"))
      (node (ref "B15") (pin "D2") (pinfunction "OUT_D2") (pintype "output"))
    )
    (net (code "110") (name "O_ACCLR") (class "Default")
      (node (ref "A18") (pin "P2") (pinfunction "P$2_P2") (pintype "bidirectional"))
      (node (ref "B18") (pin "K2") (pinfunction "IN_K2") (pintype "input"))
    )
    (net (code "111") (name "O_ADD00") (class "Default")
      (node (ref "A19") (pin "D2") (pinfunction "P$2_D2") (pintype "bidirectional"))
      (node (ref "B20") (pin "E2") (pinfunction "IN_E2") (pintype "input"))
    )
    (net (code "112") (name "O_ADD01") (class "Default")
      (node (ref "A19") (pin "E2") (pinfunction "P$2_E2") (pintype "bidirectional"))
      (node (ref "B20") (pin "H2") (pinfunction "IN_H2") (pintype "input"))
    )
    (net (code "113") (name "O_ADD02") (class "Default")
      (node (ref "A19") (pin "H2") (pinfunction "P$2_H2") (pintype "bidirectional"))
      (node (ref "B20") (pin "K2") (pinfunction "IN_K2") (pintype "input"))
    )
    (net (code "114") (name "O_ADD03") (class "Default")
      (node (ref "A19") (pin "K2") (pinfunction "P$2_K2") (pintype "bidirectional"))
      (node (ref "B20") (pin "M2") (pinfunction "IN_M2") (pintype "input"))
    )
    (net (code "115") (name "O_ADD04") (class "Default")
      (node (ref "A19") (pin "M2") (pinfunction "P$2_M2") (pintype "bidirectional"))
      (node (ref "B20") (pin "P2") (pinfunction "IN_P2") (pintype "input"))
    )
    (net (code "116") (name "O_ADD05") (class "Default")
      (node (ref "A19") (pin "P2") (pinfunction "P$2_P2") (pintype "bidirectional"))
      (node (ref "B20") (pin "S2") (pinfunction "IN_S2") (pintype "input"))
    )
    (net (code "117") (name "O_ADD06") (class "Default")
      (node (ref "A19") (pin "S2") (pinfunction "P$2_S2") (pintype "bidirectional"))
      (node (ref "B21") (pin "E2") (pinfunction "IN_E2") (pintype "input"))
    )
    (net (code "118") (name "O_ADD07") (class "Default")
      (node (ref "A19") (pin "T2") (pinfunction "P$2_T2") (pintype "bidirectional"))
      (node (ref "B21") (pin "H2") (pinfunction "IN_H2") (pintype "input"))
    )
    (net (code "119") (name "O_ADD08") (class "Default")
      (node (ref "A19") (pin "V2") (pinfunction "P$2_V2") (pintype "bidirectional"))
      (node (ref "B21") (pin "K2") (pinfunction "IN_K2") (pintype "input"))
    )
    (net (code "120") (name "O_ADD09") (class "Default")
      (node (ref "A20") (pin "D2") (pinfunction "P$2_D2") (pintype "bidirectional"))
      (node (ref "B21") (pin "M2") (pinfunction "IN_M2") (pintype "input"))
    )
    (net (code "121") (name "O_ADD10") (class "Default")
      (node (ref "A20") (pin "E2") (pinfunction "P$2_E2") (pintype "bidirectional"))
      (node (ref "B21") (pin "P2") (pinfunction "IN_P2") (pintype "input"))
    )
    (net (code "122") (name "O_ADD11") (class "Default")
      (node (ref "A20") (pin "H2") (pinfunction "P$2_H2") (pintype "bidirectional"))
      (node (ref "B21") (pin "S2") (pinfunction "IN_S2") (pintype "input"))
    )
    (net (code "123") (name "O_BAC00") (class "Default")
      (node (ref "A13") (pin "D2") (pinfunction "P$2_D2") (pintype "bidirectional"))
      (node (ref "B10") (pin "D2") (pinfunction "OUT_D2") (pintype "output"))
    )
    (net (code "124") (name "O_BAC01") (class "Default")
      (node (ref "A13") (pin "E2") (pinfunction "P$2_E2") (pintype "bidirectional"))
      (node (ref "B10") (pin "K2") (pinfunction "OUT_K2") (pintype "output"))
    )
    (net (code "125") (name "O_BAC02") (class "Default")
      (node (ref "A13") (pin "H2") (pinfunction "P$2_H2") (pintype "bidirectional"))
      (node (ref "B10") (pin "S2") (pinfunction "OUT_S2") (pintype "output"))
    )
    (net (code "126") (name "O_BAC03") (class "Default")
      (node (ref "A13") (pin "K2") (pinfunction "P$2_K2") (pintype "bidirectional"))
      (node (ref "B11") (pin "D2") (pinfunction "OUT_D2") (pintype "output"))
    )
    (net (code "127") (name "O_BAC04") (class "Default")
      (node (ref "A13") (pin "M2") (pinfunction "P$2_M2") (pintype "bidirectional"))
      (node (ref "B11") (pin "K2") (pinfunction "OUT_K2") (pintype "output"))
    )
    (net (code "128") (name "O_BAC05") (class "Default")
      (node (ref "A13") (pin "P2") (pinfunction "P$2_P2") (pintype "bidirectional"))
      (node (ref "B11") (pin "S2") (pinfunction "OUT_S2") (pintype "output"))
    )
    (net (code "129") (name "O_BAC06") (class "Default")
      (node (ref "A13") (pin "S2") (pinfunction "P$2_S2") (pintype "bidirectional"))
      (node (ref "B12") (pin "D2") (pinfunction "OUT_D2") (pintype "output"))
    )
    (net (code "130") (name "O_BAC07") (class "Default")
      (node (ref "A13") (pin "T2") (pinfunction "P$2_T2") (pintype "bidirectional"))
      (node (ref "B12") (pin "K2") (pinfunction "OUT_K2") (pintype "output"))
    )
    (net (code "131") (name "O_BAC08") (class "Default")
      (node (ref "A13") (pin "V2") (pinfunction "P$2_V2") (pintype "bidirectional"))
      (node (ref "B12") (pin "S2") (pinfunction "OUT_S2") (pintype "output"))
    )
    (net (code "132") (name "O_BAC09") (class "Default")
      (node (ref "A14") (pin "D2") (pinfunction "P$2_D2") (pintype "bidirectional"))
      (node (ref "B13") (pin "D2") (pinfunction "OUT_D2") (pintype "output"))
    )
    (net (code "133") (name "O_BAC10") (class "Default")
      (node (ref "A14") (pin "E2") (pinfunction "P$2_E2") (pintype "bidirectional"))
      (node (ref "B13") (pin "K2") (pinfunction "OUT_K2") (pintype "output"))
    )
    (net (code "134") (name "O_BAC11") (class "Default")
      (node (ref "A14") (pin "H2") (pinfunction "P$2_H2") (pintype "bidirectional"))
      (node (ref "B13") (pin "S2") (pinfunction "OUT_S2") (pintype "output"))
    )
    (net (code "135") (name "O_BREAK") (class "Default")
      (node (ref "A20") (pin "P2") (pinfunction "P$2_P2") (pintype "bidirectional"))
      (node (ref "B14") (pin "S2") (pinfunction "OUT_S2") (pintype "output"))
    )
    (net (code "136") (name "O_BRKRQ") (class "Default")
      (node (ref "A20") (pin "K2") (pinfunction "P$2_K2") (pintype "bidirectional"))
      (node (ref "B18") (pin "P2") (pinfunction "IN_P2") (pintype "input"))
    )
    (net (code "137") (name "O_CAINCR") (class "Default")
      (node (ref "A22") (pin "M2") (pinfunction "P$2_M2") (pintype "bidirectional"))
      (node (ref "B19") (pin "K2") (pinfunction "IN_K2") (pintype "input"))
    )
    (net (code "138") (name "O_DATA00") (class "Default")
      (node (ref "A21") (pin "D2") (pinfunction "P$2_D2") (pintype "bidirectional"))
      (node (ref "B22") (pin "E2") (pinfunction "IN_E2") (pintype "input"))
    )
    (net (code "139") (name "O_DATA01") (class "Default")
      (node (ref "A21") (pin "E2") (pinfunction "P$2_E2") (pintype "bidirectional"))
      (node (ref "B22") (pin "H2") (pinfunction "IN_H2") (pintype "input"))
    )
    (net (code "140") (name "O_DATA02") (class "Default")
      (node (ref "A21") (pin "H2") (pinfunction "P$2_H2") (pintype "bidirectional"))
      (node (ref "B22") (pin "K2") (pinfunction "IN_K2") (pintype "input"))
    )
    (net (code "141") (name "O_DATA03") (class "Default")
      (node (ref "A21") (pin "K2") (pinfunction "P$2_K2") (pintype "bidirectional"))
      (node (ref "B22") (pin "M2") (pinfunction "IN_M2") (pintype "input"))
    )
    (net (code "142") (name "O_DATA04") (class "Default")
      (node (ref "A21") (pin "M2") (pinfunction "P$2_M2") (pintype "bidirectional"))
      (node (ref "B22") (pin "P2") (pinfunction "IN_P2") (pintype "input"))
    )
    (net (code "143") (name "O_DATA05") (class "Default")
      (node (ref "A21") (pin "P2") (pinfunction "P$2_P2") (pintype "bidirectional"))
      (node (ref "B22") (pin "S2") (pinfunction "IN_S2") (pintype "input"))
    )
    (net (code "144") (name "O_DATA06") (class "Default")
      (node (ref "A21") (pin "S2") (pinfunction "P$2_S2") (pintype "bidirectional"))
      (node (ref "B23") (pin "E2") (pinfunction "IN_E2") (pintype "input"))
    )
    (net (code "145") (name "O_DATA07") (class "Default")
      (node (ref "A21") (pin "T2") (pinfunction "P$2_T2") (pintype "bidirectional"))
      (node (ref "B23") (pin "H2") (pinfunction "IN_H2") (pintype "input"))
    )
    (net (code "146") (name "O_DATA08") (class "Default")
      (node (ref "A21") (pin "V2") (pinfunction "P$2_V2") (pintype "bidirectional"))
      (node (ref "B23") (pin "K2") (pinfunction "IN_K2") (pintype "input"))
    )
    (net (code "147") (name "O_DATA09") (class "Default")
      (node (ref "A22") (pin "D2") (pinfunction "P$2_D2") (pintype "bidirectional"))
      (node (ref "B23") (pin "M2") (pinfunction "IN_M2") (pintype "input"))
    )
    (net (code "148") (name "O_DATA10") (class "Default")
      (node (ref "A22") (pin "E2") (pinfunction "P$2_E2") (pintype "bidirectional"))
      (node (ref "B23") (pin "P2") (pinfunction "IN_P2") (pintype "input"))
    )
    (net (code "149") (name "O_DATA11") (class "Default")
      (node (ref "A22") (pin "H2") (pinfunction "P$2_H2") (pintype "bidirectional"))
      (node (ref "B23") (pin "S2") (pinfunction "IN_S2") (pintype "input"))
    )
    (net (code "150") (name "O_DATAIN") (class "Default")
      (node (ref "A20") (pin "M2") (pinfunction "P$2_M2") (pintype "bidirectional"))
      (node (ref "B18") (pin "S2") (pinfunction "IN_S2") (pintype "input"))
    )
    (net (code "151") (name "O_EXTA0") (class "Default")
      (node (ref "A23") (pin "H2") (pinfunction "P$2_H2") (pintype "bidirectional"))
      (node (ref "B19") (pin "S2") (pinfunction "IN_S2") (pintype "input"))
    )
    (net (code "152") (name "O_EXTA1") (class "Default")
      (node (ref "A23") (pin "E2") (pinfunction "P$2_E2") (pintype "bidirectional"))
      (node (ref "B19") (pin "P2") (pinfunction "IN_P2") (pintype "input"))
    )
    (net (code "153") (name "O_EXTA2") (class "Default")
      (node (ref "A23") (pin "D2") (pinfunction "P$2_D2") (pintype "bidirectional"))
      (node (ref "B19") (pin "M2") (pinfunction "IN_M2") (pintype "input"))
    )
    (net (code "154") (name "O_INIT") (class "Default")
      (node (ref "A14") (pin "V2") (pinfunction "P$2_V2") (pintype "bidirectional"))
      (node (ref "B09") (pin "S2") (pinfunction "OUT_S2") (pintype "output"))
    )
    (net (code "155") (name "O_IOP1") (class "Default")
      (node (ref "A14") (pin "K2") (pinfunction "P$2_K2") (pintype "bidirectional"))
      (node (ref "B08") (pin "D2") (pinfunction "OUT_D2") (pintype "output"))
    )
    (net (code "156") (name "O_IOP2") (class "Default")
      (node (ref "A14") (pin "M2") (pinfunction "P$2_M2") (pintype "bidirectional"))
      (node (ref "B08") (pin "K2") (pinfunction "OUT_K2") (pintype "output"))
    )
    (net (code "157") (name "O_IOP4") (class "Default")
      (node (ref "A14") (pin "P2") (pinfunction "P$2_P2") (pintype "bidirectional"))
      (node (ref "B08") (pin "S2") (pinfunction "OUT_S2") (pintype "output"))
    )
    (net (code "158") (name "O_IRQ") (class "Default")
      (node (ref "A18") (pin "M2") (pinfunction "P$2_M2") (pintype "bidirectional"))
      (node (ref "B18") (pin "H2") (pinfunction "IN_H2") (pintype "input"))
    )
    (net (code "159") (name "O_LINE") (class "Default")
      (node (ref "A18") (pin "V2") (pinfunction "P$2_V2") (pintype "bidirectional"))
      (node (ref "B18") (pin "M2") (pinfunction "IN_M2") (pintype "input"))
    )
    (net (code "160") (name "O_MB00") (class "Default")
      (node (ref "A07") (pin "D2") (pinfunction "OUT_D2") (pintype "output"))
      (node (ref "A15") (pin "D2") (pinfunction "P$2_D2") (pintype "bidirectional"))
    )
    (net (code "161") (name "O_MB01") (class "Default")
      (node (ref "A07") (pin "K2") (pinfunction "OUT_K2") (pintype "output"))
      (node (ref "A15") (pin "E2") (pinfunction "P$2_E2") (pintype "bidirectional"))
    )
    (net (code "162") (name "O_MB02") (class "Default")
      (node (ref "A07") (pin "S2") (pinfunction "OUT_S2") (pintype "output"))
      (node (ref "A15") (pin "H2") (pinfunction "P$2_H2") (pintype "bidirectional"))
    )
    (net (code "163") (name "O_MB03") (class "Default")
      (node (ref "A08") (pin "K2") (pinfunction "OUT_K2") (pintype "output"))
      (node (ref "A15") (pin "M2") (pinfunction "P$2_M2") (pintype "bidirectional"))
    )
    (net (code "164") (name "O_MB04") (class "Default")
      (node (ref "A09") (pin "D2") (pinfunction "OUT_D2") (pintype "output"))
      (node (ref "A15") (pin "S2") (pinfunction "P$2_S2") (pintype "bidirectional"))
    )
    (net (code "165") (name "O_MB05") (class "Default")
      (node (ref "A09") (pin "S2") (pinfunction "OUT_S2") (pintype "output"))
      (node (ref "A15") (pin "V2") (pinfunction "P$2_V2") (pintype "bidirectional"))
    )
    (net (code "166") (name "O_MB06") (class "Default")
      (node (ref "A10") (pin "K2") (pinfunction "OUT_K2") (pintype "output"))
      (node (ref "A16") (pin "E2") (pinfunction "P$2_E2") (pintype "bidirectional"))
    )
    (net (code "167") (name "O_MB07") (class "Default")
      (node (ref "A11") (pin "D2") (pinfunction "OUT_D2") (pintype "output"))
      (node (ref "A16") (pin "K2") (pinfunction "P$2_K2") (pintype "bidirectional"))
    )
    (net (code "168") (name "O_MB08") (class "Default")
      (node (ref "A11") (pin "S2") (pinfunction "OUT_S2") (pintype "output"))
      (node (ref "A16") (pin "P2") (pinfunction "P$2_P2") (pintype "bidirectional"))
    )
    (net (code "169") (name "O_MB09") (class "Default")
      (node (ref "A12") (pin "D2") (pinfunction "OUT_D2") (pintype "output"))
      (node (ref "A16") (pin "S2") (pinfunction "P$2_S2") (pintype "bidirectional"))
    )
    (net (code "170") (name "O_MB10") (class "Default")
      (node (ref "A12") (pin "K2") (pinfunction "OUT_K2") (pintype "output"))
      (node (ref "A16") (pin "T2") (pinfunction "P$2_T2") (pintype "bidirectional"))
    )
    (net (code "171") (name "O_MB11") (class "Default")
      (node (ref "A12") (pin "S2") (pinfunction "OUT_S2") (pintype "output"))
      (node (ref "A16") (pin "V2") (pinfunction "P$2_V2") (pintype "bidirectional"))
    )
    (net (code "172") (name "O_MBINCR") (class "Default")
      (node (ref "A20") (pin "T2") (pinfunction "P$2_T2") (pintype "bidirectional"))
      (node (ref "B19") (pin "E2") (pinfunction "IN_E2") (pintype "input"))
    )
    (net (code "173") (name "O_RUN") (class "Default")
      (node (ref "A18") (pin "S2") (pinfunction "P$2_S2") (pintype "bidirectional"))
      (node (ref "B14") (pin "D2") (pinfunction "OUT_D2") (pintype "output"))
    )
    (net (code "174") (name "O_SKIP") (class "Default")
      (node (ref "A18") (pin "K2") (pinfunction "P$2_K2") (pintype "bidirectional"))
      (node (ref "B18") (pin "E2") (pinfunction "IN_E2") (pintype "input"))
    )
    (net (code "175") (name "O_TS1") (class "Default")
      (node (ref "A14") (pin "T2") (pinfunction "P$2_T2") (pintype "bidirectional"))
      (node (ref "B09") (pin "K2") (pinfunction "OUT_K2") (pintype "output"))
    )
    (net (code "176") (name "O_TS3") (class "Default")
      (node (ref "A14") (pin "S2") (pinfunction "P$2_S2") (pintype "bidirectional"))
      (node (ref "B09") (pin "D2") (pinfunction "OUT_D2") (pintype "output"))
    )
    (net (code "177") (name "O_TT_INST") (class "Default")
      (node (ref "A18") (pin "T2") (pinfunction "P$2_T2") (pintype "bidirectional"))
      (node (ref "B14") (pin "K2") (pinfunction "OUT_K2") (pintype "output"))
    )
    (net (code "178") (name "O_WCOV") (class "Default")
      (node (ref "A22") (pin "P2") (pinfunction "P$2_P2") (pintype "bidirectional"))
      (node (ref "B15") (pin "K2") (pinfunction "OUT_K2") (pintype "output"))
    )
    (net (code "180") (name "unconnected-(A07A-SLOW-PadE2)") (class "Default")
      (node (ref "A07") (pin "E2") (pinfunction "SLOW_E2") (pintype "passive"))
    )
    (net (code "181") (name "unconnected-(A07D-SLOW-PadL2)") (class "Default")
      (node (ref "A07") (pin "L2") (pinfunction "SLOW_L2") (pintype "passive"))
    )
    (net (code "182") (name "unconnected-(A07E-SLOW-PadR2)") (class "Default")
      (node (ref "A07") (pin "R2") (pinfunction "SLOW_R2") (pintype "passive"))
    )
    (net (code "183") (name "unconnected-(A08A-SLOW-PadE2)") (class "Default")
      (node (ref "A08") (pin "E2") (pinfunction "SLOW_E2") (pintype "passive"))
    )
    (net (code "184") (name "unconnected-(A08D-SLOW-PadL2)") (class "Default")
      (node (ref "A08") (pin "L2") (pinfunction "SLOW_L2") (pintype "passive"))
    )
    (net (code "185") (name "unconnected-(A08E-SLOW-PadR2)") (class "Default")
      (node (ref "A08") (pin "R2") (pinfunction "SLOW_R2") (pintype "passive"))
    )
    (net (code "186") (name "unconnected-(A09A-SLOW-PadE2)") (class "Default")
      (node (ref "A09") (pin "E2") (pinfunction "SLOW_E2") (pintype "passive"))
    )
    (net (code "187") (name "unconnected-(A09D-SLOW-PadL2)") (class "Default")
      (node (ref "A09") (pin "L2") (pinfunction "SLOW_L2") (pintype "passive"))
    )
    (net (code "188") (name "unconnected-(A09E-SLOW-PadR2)") (class "Default")
      (node (ref "A09") (pin "R2") (pinfunction "SLOW_R2") (pintype "passive"))
    )
    (net (code "189") (name "unconnected-(A10A-SLOW-PadE2)") (class "Default")
      (node (ref "A10") (pin "E2") (pinfunction "SLOW_E2") (pintype "passive"))
    )
    (net (code "190") (name "unconnected-(A10D-SLOW-PadL2)") (class "Default")
      (node (ref "A10") (pin "L2") (pinfunction "SLOW_L2") (pintype "passive"))
    )
    (net (code "191") (name "unconnected-(A10E-SLOW-PadR2)") (class "Default")
      (node (ref "A10") (pin "R2") (pinfunction "SLOW_R2") (pintype "passive"))
    )
    (net (code "192") (name "unconnected-(A11A-SLOW-PadE2)") (class "Default")
      (node (ref "A11") (pin "E2") (pinfunction "SLOW_E2") (pintype "passive"))
    )
    (net (code "193") (name "unconnected-(A11D-SLOW-PadL2)") (class "Default")
      (node (ref "A11") (pin "L2") (pinfunction "SLOW_L2") (pintype "passive"))
    )
    (net (code "194") (name "unconnected-(A11E-SLOW-PadR2)") (class "Default")
      (node (ref "A11") (pin "R2") (pinfunction "SLOW_R2") (pintype "passive"))
    )
    (net (code "195") (name "unconnected-(A12A-SLOW-PadE2)") (class "Default")
      (node (ref "A12") (pin "E2") (pinfunction "SLOW_E2") (pintype "passive"))
    )
    (net (code "196") (name "unconnected-(A12D-SLOW-PadL2)") (class "Default")
      (node (ref "A12") (pin "L2") (pinfunction "SLOW_L2") (pintype "passive"))
    )
    (net (code "197") (name "unconnected-(A12E-SLOW-PadR2)") (class "Default")
      (node (ref "A12") (pin "R2") (pinfunction "SLOW_R2") (pintype "passive"))
    )
    (net (code "198") (name "unconnected-(B08A-SLOW-PadE2)") (class "Default")
      (node (ref "B08") (pin "E2") (pinfunction "SLOW_E2") (pintype "passive"))
    )
    (net (code "199") (name "unconnected-(B08D-SLOW-PadL2)") (class "Default")
      (node (ref "B08") (pin "L2") (pinfunction "SLOW_L2") (pintype "passive"))
    )
    (net (code "200") (name "unconnected-(B08E-SLOW-PadR2)") (class "Default")
      (node (ref "B08") (pin "R2") (pinfunction "SLOW_R2") (pintype "passive"))
    )
    (net (code "201") (name "unconnected-(B09A-SLOW-PadE2)") (class "Default")
      (node (ref "B09") (pin "E2") (pinfunction "SLOW_E2") (pintype "passive"))
    )
    (net (code "202") (name "unconnected-(B09D-SLOW-PadL2)") (class "Default")
      (node (ref "B09") (pin "L2") (pinfunction "SLOW_L2") (pintype "passive"))
    )
    (net (code "203") (name "unconnected-(B09E-SLOW-PadR2)") (class "Default")
      (node (ref "B09") (pin "R2") (pinfunction "SLOW_R2") (pintype "passive"))
    )
    (net (code "204") (name "unconnected-(B10A-SLOW-PadE2)") (class "Default")
      (node (ref "B10") (pin "E2") (pinfunction "SLOW_E2") (pintype "passive"))
    )
    (net (code "205") (name "unconnected-(B10D-SLOW-PadL2)") (class "Default")
      (node (ref "B10") (pin "L2") (pinfunction "SLOW_L2") (pintype "passive"))
    )
    (net (code "206") (name "unconnected-(B10E-SLOW-PadR2)") (class "Default")
      (node (ref "B10") (pin "R2") (pinfunction "SLOW_R2") (pintype "passive"))
    )
    (net (code "207") (name "unconnected-(B11A-SLOW-PadE2)") (class "Default")
      (node (ref "B11") (pin "E2") (pinfunction "SLOW_E2") (pintype "passive"))
    )
    (net (code "208") (name "unconnected-(B11D-SLOW-PadL2)") (class "Default")
      (node (ref "B11") (pin "L2") (pinfunction "SLOW_L2") (pintype "passive"))
    )
    (net (code "209") (name "unconnected-(B11E-SLOW-PadR2)") (class "Default")
      (node (ref "B11") (pin "R2") (pinfunction "SLOW_R2") (pintype "passive"))
    )
    (net (code "210") (name "unconnected-(B12A-SLOW-PadE2)") (class "Default")
      (node (ref "B12") (pin "E2") (pinfunction "SLOW_E2") (pintype "passive"))
    )
    (net (code "211") (name "unconnected-(B12D-SLOW-PadL2)") (class "Default")
      (node (ref "B12") (pin "L2") (pinfunction "SLOW_L2") (pintype "passive"))
    )
    (net (code "212") (name "unconnected-(B12E-SLOW-PadR2)") (class "Default")
      (node (ref "B12") (pin "R2") (pinfunction "SLOW_R2") (pintype "passive"))
    )
    (net (code "213") (name "unconnected-(B13A-SLOW-PadE2)") (class "Default")
      (node (ref "B13") (pin "E2") (pinfunction "SLOW_E2") (pintype "passive"))
    )
    (net (code "214") (name "unconnected-(B13D-SLOW-PadL2)") (class "Default")
      (node (ref "B13") (pin "L2") (pinfunction "SLOW_L2") (pintype "passive"))
    )
    (net (code "215") (name "unconnected-(B13E-SLOW-PadR2)") (class "Default")
      (node (ref "B13") (pin "R2") (pinfunction "SLOW_R2") (pintype "passive"))
    )
    (net (code "216") (name "unconnected-(B14A-SLOW-PadE2)") (class "Default")
      (node (ref "B14") (pin "E2") (pinfunction "SLOW_E2") (pintype "passive"))
    )
    (net (code "217") (name "unconnected-(B14D-SLOW-PadL2)") (class "Default")
      (node (ref "B14") (pin "L2") (pinfunction "SLOW_L2") (pintype "passive"))
    )
    (net (code "218") (name "unconnected-(B14E-SLOW-PadR2)") (class "Default")
      (node (ref "B14") (pin "R2") (pinfunction "SLOW_R2") (pintype "passive"))
    )
    (net (code "219") (name "unconnected-(B15A-SLOW-PadE2)") (class "Default")
      (node (ref "B15") (pin "E2") (pinfunction "SLOW_E2") (pintype "passive"))
    )
    (net (code "220") (name "unconnected-(B15D-SLOW-PadL2)") (class "Default")
      (node (ref "B15") (pin "L2") (pinfunction "SLOW_L2") (pintype "passive"))
    )
    (net (code "221") (name "~{I_MB03}") (class "Default")
      (node (ref "A02") (pin "H1") (pinfunction "P$2_H1") (pintype "bidirectional"))
      (node (ref "A06") (pin "H1") (pinfunction "CATHODE_H1") (pintype "passive"))
      (node (ref "A08") (pin "H2") (pinfunction "IN2_H2") (pintype "input"))
      (node (ref "B02") (pin "H1") (pinfunction "P$2_H1") (pintype "bidirectional"))
    )
    (net (code "222") (name "~{I_MB04}") (class "Default")
      (node (ref "A02") (pin "L1") (pinfunction "P$2_L1") (pintype "bidirectional"))
      (node (ref "A06") (pin "L1") (pinfunction "CATHODE_L1") (pintype "passive"))
      (node (ref "A08") (pin "U2") (pinfunction "IN2_U2") (pintype "input"))
      (node (ref "B02") (pin "L1") (pinfunction "P$2_L1") (pintype "bidirectional"))
    )
    (net (code "223") (name "~{I_MB05}") (class "Default")
      (node (ref "A02") (pin "P1") (pinfunction "P$2_P1") (pintype "bidirectional"))
      (node (ref "A06") (pin "P1") (pinfunction "CATHODE_P1") (pintype "passive"))
      (node (ref "A09") (pin "N2") (pinfunction "IN2_N2") (pintype "input"))
      (node (ref "B02") (pin "P1") (pinfunction "P$2_P1") (pintype "bidirectional"))
    )
    (net (code "224") (name "~{I_MB06}") (class "Default")
      (node (ref "A02") (pin "D2") (pinfunction "P$2_D2") (pintype "bidirectional"))
      (node (ref "A06") (pin "D2") (pinfunction "CATHODE_D2") (pintype "passive"))
      (node (ref "A10") (pin "H2") (pinfunction "IN2_H2") (pintype "input"))
      (node (ref "B02") (pin "D2") (pinfunction "P$2_D2") (pintype "bidirectional"))
    )
    (net (code "225") (name "~{I_MB07}") (class "Default")
      (node (ref "A02") (pin "H2") (pinfunction "P$2_H2") (pintype "bidirectional"))
      (node (ref "A06") (pin "H2") (pinfunction "CATHODE_H2") (pintype "passive"))
      (node (ref "A10") (pin "U2") (pinfunction "IN2_U2") (pintype "input"))
      (node (ref "B02") (pin "H2") (pinfunction "P$2_H2") (pintype "bidirectional"))
    )
    (net (code "226") (name "~{I_MB08}") (class "Default")
      (node (ref "A02") (pin "M2") (pinfunction "P$2_M2") (pintype "bidirectional"))
      (node (ref "A06") (pin "M2") (pinfunction "CATHODE_M2") (pintype "passive"))
      (node (ref "A11") (pin "N2") (pinfunction "IN2_N2") (pintype "input"))
      (node (ref "B02") (pin "M2") (pinfunction "P$2_M2") (pintype "bidirectional"))
    )
    (net (code "227") (name "~{O_MB03}") (class "Default")
      (node (ref "A08") (pin "D2") (pinfunction "OUT_D2") (pintype "output"))
      (node (ref "A15") (pin "K2") (pinfunction "P$2_K2") (pintype "bidirectional"))
    )
    (net (code "228") (name "~{O_MB04}") (class "Default")
      (node (ref "A08") (pin "S2") (pinfunction "OUT_S2") (pintype "output"))
      (node (ref "A15") (pin "P2") (pinfunction "P$2_P2") (pintype "bidirectional"))
    )
    (net (code "229") (name "~{O_MB05}") (class "Default")
      (node (ref "A09") (pin "K2") (pinfunction "OUT_K2") (pintype "output"))
      (node (ref "A15") (pin "T2") (pinfunction "P$2_T2") (pintype "bidirectional"))
    )
    (net (code "230") (name "~{O_MB06}") (class "Default")
      (node (ref "A10") (pin "D2") (pinfunction "OUT_D2") (pintype "output"))
      (node (ref "A16") (pin "D2") (pinfunction "P$2_D2") (pintype "bidirectional"))
    )
    (net (code "231") (name "~{O_MB07}") (class "Default")
      (node (ref "A10") (pin "S2") (pinfunction "OUT_S2") (pintype "output"))
      (node (ref "A16") (pin "H2") (pinfunction "P$2_H2") (pintype "bidirectional"))
    )
    (net (code "232") (name "~{O_MB08}") (class "Default")
      (node (ref "A11") (pin "K2") (pinfunction "OUT_K2") (pintype "output"))
      (node (ref "A16") (pin "M2") (pinfunction "P$2_M2") (pintype "bidirectional"))
    )
  )
)
